# RELAYS.net
KiCad netlist of a schematic drawn in Altium Designer
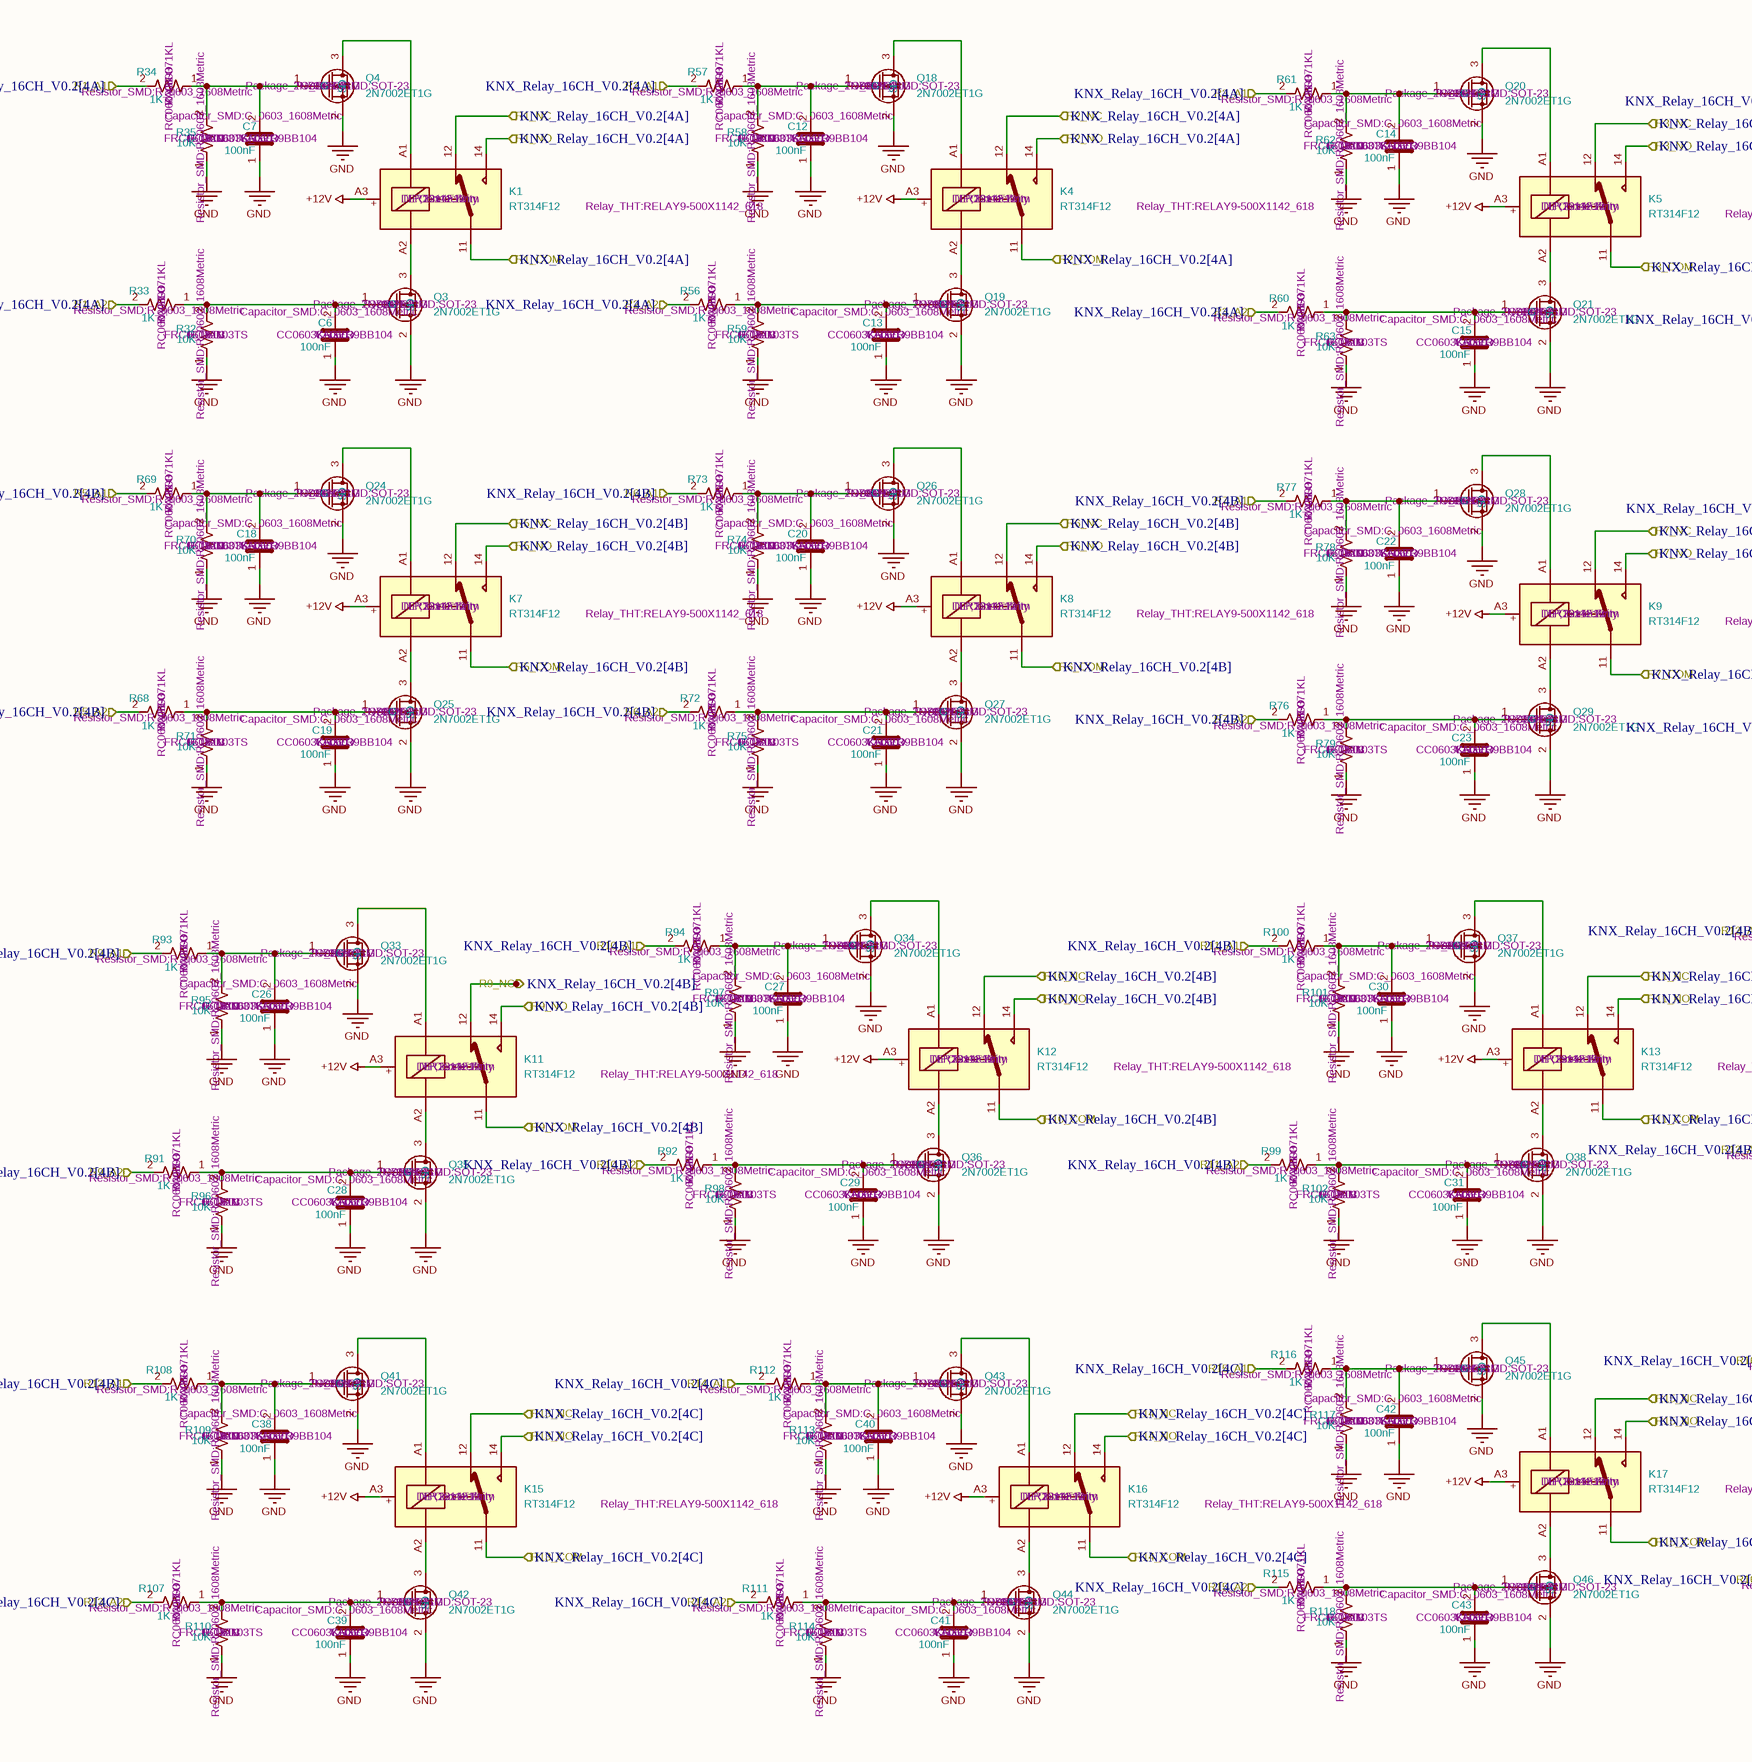
[diagram p0: RELAYS.SchDoc, left]
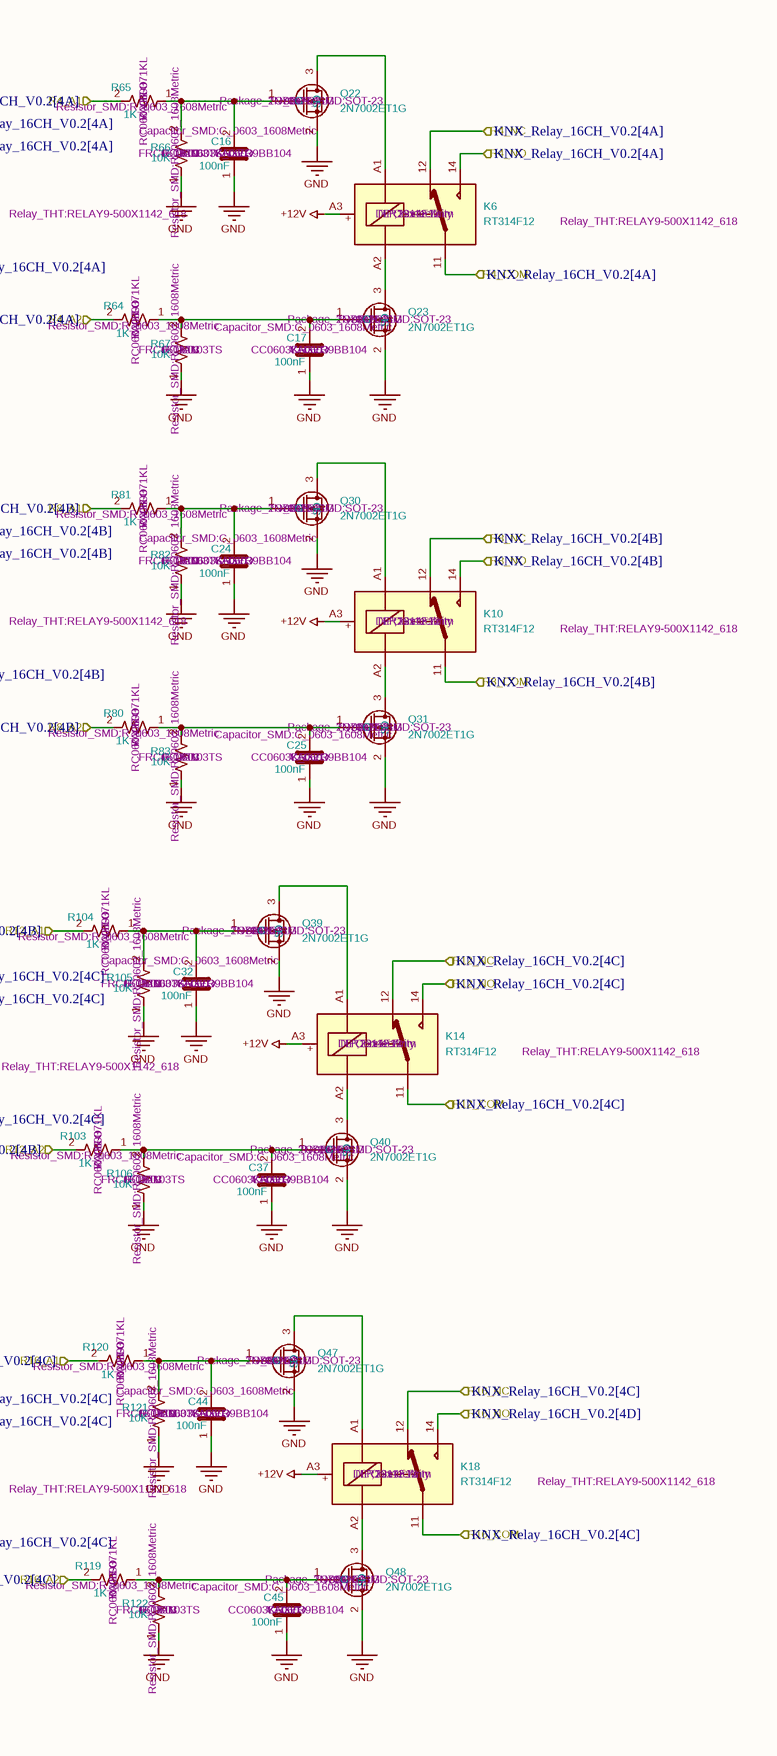
[diagram p1: RELAYS.SchDoc, right]

(export (version "E")
  (design (tool "Eeschema 10.0.6"))
  (components
    (comp (ref "C6")
      (value "100nF")
      (footprint "Capacitor_SMD:C_0603_1608Metric")
      (fields
        (field (name "MANUFACTURER PART NUMBER") "CC0603KRX7R9BB104")
        (field (name "MANUFACTURER") "YAGEO")
        (field (name "PACKAGE") "C_0603")
      )
      (libsource (lib "*") (part "C_3"))
    )
    (comp (ref "C7")
      (value "100nF")
      (footprint "Capacitor_SMD:C_0603_1608Metric")
      (fields
        (field (name "MANUFACTURER PART NUMBER") "CC0603KRX7R9BB104")
        (field (name "MANUFACTURER") "YAGEO")
        (field (name "PACKAGE") "C_0603")
      )
      (libsource (lib "*") (part "C_3"))
    )
    (comp (ref "C12")
      (value "100nF")
      (footprint "Capacitor_SMD:C_0603_1608Metric")
      (fields
        (field (name "MANUFACTURER PART NUMBER") "CC0603KRX7R9BB104")
        (field (name "MANUFACTURER") "YAGEO")
        (field (name "PACKAGE") "C_0603")
      )
      (libsource (lib "*") (part "C_3"))
    )
    (comp (ref "C13")
      (value "100nF")
      (footprint "Capacitor_SMD:C_0603_1608Metric")
      (fields
        (field (name "MANUFACTURER PART NUMBER") "CC0603KRX7R9BB104")
        (field (name "MANUFACTURER") "YAGEO")
        (field (name "PACKAGE") "C_0603")
      )
      (libsource (lib "*") (part "C_3"))
    )
    (comp (ref "C14")
      (value "100nF")
      (footprint "Capacitor_SMD:C_0603_1608Metric")
      (fields
        (field (name "MANUFACTURER PART NUMBER") "CC0603KRX7R9BB104")
        (field (name "MANUFACTURER") "YAGEO")
        (field (name "PACKAGE") "C_0603")
      )
      (libsource (lib "*") (part "C_3"))
    )
    (comp (ref "C15")
      (value "100nF")
      (footprint "Capacitor_SMD:C_0603_1608Metric")
      (fields
        (field (name "MANUFACTURER PART NUMBER") "CC0603KRX7R9BB104")
        (field (name "MANUFACTURER") "YAGEO")
        (field (name "PACKAGE") "C_0603")
      )
      (libsource (lib "*") (part "C_3"))
    )
    (comp (ref "C16")
      (value "100nF")
      (footprint "Capacitor_SMD:C_0603_1608Metric")
      (fields
        (field (name "MANUFACTURER PART NUMBER") "CC0603KRX7R9BB104")
        (field (name "MANUFACTURER") "YAGEO")
        (field (name "PACKAGE") "C_0603")
      )
      (libsource (lib "*") (part "C_3"))
    )
    (comp (ref "C17")
      (value "100nF")
      (footprint "Capacitor_SMD:C_0603_1608Metric")
      (fields
        (field (name "MANUFACTURER PART NUMBER") "CC0603KRX7R9BB104")
        (field (name "MANUFACTURER") "YAGEO")
        (field (name "PACKAGE") "C_0603")
      )
      (libsource (lib "*") (part "C_3"))
    )
    (comp (ref "C18")
      (value "100nF")
      (footprint "Capacitor_SMD:C_0603_1608Metric")
      (fields
        (field (name "MANUFACTURER PART NUMBER") "CC0603KRX7R9BB104")
        (field (name "MANUFACTURER") "YAGEO")
        (field (name "PACKAGE") "C_0603")
      )
      (libsource (lib "*") (part "C_3"))
    )
    (comp (ref "C19")
      (value "100nF")
      (footprint "Capacitor_SMD:C_0603_1608Metric")
      (fields
        (field (name "MANUFACTURER PART NUMBER") "CC0603KRX7R9BB104")
        (field (name "MANUFACTURER") "YAGEO")
        (field (name "PACKAGE") "C_0603")
      )
      (libsource (lib "*") (part "C_3"))
    )
    (comp (ref "C20")
      (value "100nF")
      (footprint "Capacitor_SMD:C_0603_1608Metric")
      (fields
        (field (name "MANUFACTURER PART NUMBER") "CC0603KRX7R9BB104")
        (field (name "MANUFACTURER") "YAGEO")
        (field (name "PACKAGE") "C_0603")
      )
      (libsource (lib "*") (part "C_3"))
    )
    (comp (ref "C21")
      (value "100nF")
      (footprint "Capacitor_SMD:C_0603_1608Metric")
      (fields
        (field (name "MANUFACTURER PART NUMBER") "CC0603KRX7R9BB104")
        (field (name "MANUFACTURER") "YAGEO")
        (field (name "PACKAGE") "C_0603")
      )
      (libsource (lib "*") (part "C_3"))
    )
    (comp (ref "C22")
      (value "100nF")
      (footprint "Capacitor_SMD:C_0603_1608Metric")
      (fields
        (field (name "MANUFACTURER PART NUMBER") "CC0603KRX7R9BB104")
        (field (name "MANUFACTURER") "YAGEO")
        (field (name "PACKAGE") "C_0603")
      )
      (libsource (lib "*") (part "C_3"))
    )
    (comp (ref "C23")
      (value "100nF")
      (footprint "Capacitor_SMD:C_0603_1608Metric")
      (fields
        (field (name "MANUFACTURER PART NUMBER") "CC0603KRX7R9BB104")
        (field (name "MANUFACTURER") "YAGEO")
        (field (name "PACKAGE") "C_0603")
      )
      (libsource (lib "*") (part "C_3"))
    )
    (comp (ref "C24")
      (value "100nF")
      (footprint "Capacitor_SMD:C_0603_1608Metric")
      (fields
        (field (name "MANUFACTURER PART NUMBER") "CC0603KRX7R9BB104")
        (field (name "MANUFACTURER") "YAGEO")
        (field (name "PACKAGE") "C_0603")
      )
      (libsource (lib "*") (part "C_3"))
    )
    (comp (ref "C25")
      (value "100nF")
      (footprint "Capacitor_SMD:C_0603_1608Metric")
      (fields
        (field (name "MANUFACTURER PART NUMBER") "CC0603KRX7R9BB104")
        (field (name "MANUFACTURER") "YAGEO")
        (field (name "PACKAGE") "C_0603")
      )
      (libsource (lib "*") (part "C_3"))
    )
    (comp (ref "C26")
      (value "100nF")
      (footprint "Capacitor_SMD:C_0603_1608Metric")
      (fields
        (field (name "MANUFACTURER PART NUMBER") "CC0603KRX7R9BB104")
        (field (name "MANUFACTURER") "YAGEO")
        (field (name "PACKAGE") "C_0603")
      )
      (libsource (lib "*") (part "C_3"))
    )
    (comp (ref "C27")
      (value "100nF")
      (footprint "Capacitor_SMD:C_0603_1608Metric")
      (fields
        (field (name "MANUFACTURER PART NUMBER") "CC0603KRX7R9BB104")
        (field (name "MANUFACTURER") "YAGEO")
        (field (name "PACKAGE") "C_0603")
      )
      (libsource (lib "*") (part "C_3"))
    )
    (comp (ref "C28")
      (value "100nF")
      (footprint "Capacitor_SMD:C_0603_1608Metric")
      (fields
        (field (name "MANUFACTURER PART NUMBER") "CC0603KRX7R9BB104")
        (field (name "MANUFACTURER") "YAGEO")
        (field (name "PACKAGE") "C_0603")
      )
      (libsource (lib "*") (part "C_3"))
    )
    (comp (ref "C29")
      (value "100nF")
      (footprint "Capacitor_SMD:C_0603_1608Metric")
      (fields
        (field (name "MANUFACTURER PART NUMBER") "CC0603KRX7R9BB104")
        (field (name "MANUFACTURER") "YAGEO")
        (field (name "PACKAGE") "C_0603")
      )
      (libsource (lib "*") (part "C_3"))
    )
    (comp (ref "C30")
      (value "100nF")
      (footprint "Capacitor_SMD:C_0603_1608Metric")
      (fields
        (field (name "MANUFACTURER PART NUMBER") "CC0603KRX7R9BB104")
        (field (name "MANUFACTURER") "YAGEO")
        (field (name "PACKAGE") "C_0603")
      )
      (libsource (lib "*") (part "C_3"))
    )
    (comp (ref "C31")
      (value "100nF")
      (footprint "Capacitor_SMD:C_0603_1608Metric")
      (fields
        (field (name "MANUFACTURER PART NUMBER") "CC0603KRX7R9BB104")
        (field (name "MANUFACTURER") "YAGEO")
        (field (name "PACKAGE") "C_0603")
      )
      (libsource (lib "*") (part "C_3"))
    )
    (comp (ref "C32")
      (value "100nF")
      (footprint "Capacitor_SMD:C_0603_1608Metric")
      (fields
        (field (name "MANUFACTURER PART NUMBER") "CC0603KRX7R9BB104")
        (field (name "MANUFACTURER") "YAGEO")
        (field (name "PACKAGE") "C_0603")
      )
      (libsource (lib "*") (part "C_3"))
    )
    (comp (ref "C37")
      (value "100nF")
      (footprint "Capacitor_SMD:C_0603_1608Metric")
      (fields
        (field (name "MANUFACTURER PART NUMBER") "CC0603KRX7R9BB104")
        (field (name "MANUFACTURER") "YAGEO")
        (field (name "PACKAGE") "C_0603")
      )
      (libsource (lib "*") (part "C_3"))
    )
    (comp (ref "C38")
      (value "100nF")
      (footprint "Capacitor_SMD:C_0603_1608Metric")
      (fields
        (field (name "MANUFACTURER PART NUMBER") "CC0603KRX7R9BB104")
        (field (name "MANUFACTURER") "YAGEO")
        (field (name "PACKAGE") "C_0603")
      )
      (libsource (lib "*") (part "C_3"))
    )
    (comp (ref "C39")
      (value "100nF")
      (footprint "Capacitor_SMD:C_0603_1608Metric")
      (fields
        (field (name "MANUFACTURER PART NUMBER") "CC0603KRX7R9BB104")
        (field (name "MANUFACTURER") "YAGEO")
        (field (name "PACKAGE") "C_0603")
      )
      (libsource (lib "*") (part "C_3"))
    )
    (comp (ref "C40")
      (value "100nF")
      (footprint "Capacitor_SMD:C_0603_1608Metric")
      (fields
        (field (name "MANUFACTURER PART NUMBER") "CC0603KRX7R9BB104")
        (field (name "MANUFACTURER") "YAGEO")
        (field (name "PACKAGE") "C_0603")
      )
      (libsource (lib "*") (part "C_3"))
    )
    (comp (ref "C41")
      (value "100nF")
      (footprint "Capacitor_SMD:C_0603_1608Metric")
      (fields
        (field (name "MANUFACTURER PART NUMBER") "CC0603KRX7R9BB104")
        (field (name "MANUFACTURER") "YAGEO")
        (field (name "PACKAGE") "C_0603")
      )
      (libsource (lib "*") (part "C_3"))
    )
    (comp (ref "C42")
      (value "100nF")
      (footprint "Capacitor_SMD:C_0603_1608Metric")
      (fields
        (field (name "MANUFACTURER PART NUMBER") "CC0603KRX7R9BB104")
        (field (name "MANUFACTURER") "YAGEO")
        (field (name "PACKAGE") "C_0603")
      )
      (libsource (lib "*") (part "C_3"))
    )
    (comp (ref "C43")
      (value "100nF")
      (footprint "Capacitor_SMD:C_0603_1608Metric")
      (fields
        (field (name "MANUFACTURER PART NUMBER") "CC0603KRX7R9BB104")
        (field (name "MANUFACTURER") "YAGEO")
        (field (name "PACKAGE") "C_0603")
      )
      (libsource (lib "*") (part "C_3"))
    )
    (comp (ref "C44")
      (value "100nF")
      (footprint "Capacitor_SMD:C_0603_1608Metric")
      (fields
        (field (name "MANUFACTURER PART NUMBER") "CC0603KRX7R9BB104")
        (field (name "MANUFACTURER") "YAGEO")
        (field (name "PACKAGE") "C_0603")
      )
      (libsource (lib "*") (part "C_3"))
    )
    (comp (ref "C45")
      (value "100nF")
      (footprint "Capacitor_SMD:C_0603_1608Metric")
      (fields
        (field (name "MANUFACTURER PART NUMBER") "CC0603KRX7R9BB104")
        (field (name "MANUFACTURER") "YAGEO")
        (field (name "PACKAGE") "C_0603")
      )
      (libsource (lib "*") (part "C_3"))
    )
    (comp (ref "K1")
      (value "RT314F12")
      (footprint "Relay_THT:RELAY9-500X1142_618")
      (fields
        (field (name "MANUFACTURER PART NUMBER") "RT314F12")
        (field (name "MANUFACTURER") "TE Connectivity")
        (field (name "PACKAGE") "DIP,29x12.7mm")
      )
      (libsource (lib "Me_Library") (part "RT314A03"))
    )
    (comp (ref "K4")
      (value "RT314F12")
      (footprint "Relay_THT:RELAY9-500X1142_618")
      (fields
        (field (name "MANUFACTURER PART NUMBER") "RT314F12")
        (field (name "MANUFACTURER") "TE Connectivity")
        (field (name "PACKAGE") "DIP,29x12.7mm")
      )
      (libsource (lib "Me_Library") (part "RT314A03"))
    )
    (comp (ref "K5")
      (value "RT314F12")
      (footprint "Relay_THT:RELAY9-500X1142_618")
      (fields
        (field (name "MANUFACTURER PART NUMBER") "RT314F12")
        (field (name "MANUFACTURER") "TE Connectivity")
        (field (name "PACKAGE") "DIP,29x12.7mm")
      )
      (libsource (lib "Me_Library") (part "RT314A03"))
    )
    (comp (ref "K6")
      (value "RT314F12")
      (footprint "Relay_THT:RELAY9-500X1142_618")
      (fields
        (field (name "MANUFACTURER PART NUMBER") "RT314F12")
        (field (name "MANUFACTURER") "TE Connectivity")
        (field (name "PACKAGE") "DIP,29x12.7mm")
      )
      (libsource (lib "Me_Library") (part "RT314A03"))
    )
    (comp (ref "K7")
      (value "RT314F12")
      (footprint "Relay_THT:RELAY9-500X1142_618")
      (fields
        (field (name "MANUFACTURER PART NUMBER") "RT314F12")
        (field (name "MANUFACTURER") "TE Connectivity")
        (field (name "PACKAGE") "DIP,29x12.7mm")
      )
      (libsource (lib "Me_Library") (part "RT314A03"))
    )
    (comp (ref "K8")
      (value "RT314F12")
      (footprint "Relay_THT:RELAY9-500X1142_618")
      (fields
        (field (name "MANUFACTURER PART NUMBER") "RT314F12")
        (field (name "MANUFACTURER") "TE Connectivity")
        (field (name "PACKAGE") "DIP,29x12.7mm")
      )
      (libsource (lib "Me_Library") (part "RT314A03"))
    )
    (comp (ref "K9")
      (value "RT314F12")
      (footprint "Relay_THT:RELAY9-500X1142_618")
      (fields
        (field (name "MANUFACTURER PART NUMBER") "RT314F12")
        (field (name "MANUFACTURER") "TE Connectivity")
        (field (name "PACKAGE") "DIP,29x12.7mm")
      )
      (libsource (lib "Me_Library") (part "RT314A03"))
    )
    (comp (ref "K10")
      (value "RT314F12")
      (footprint "Relay_THT:RELAY9-500X1142_618")
      (fields
        (field (name "MANUFACTURER PART NUMBER") "RT314F12")
        (field (name "MANUFACTURER") "TE Connectivity")
        (field (name "PACKAGE") "DIP,29x12.7mm")
      )
      (libsource (lib "Me_Library") (part "RT314A03"))
    )
    (comp (ref "K11")
      (value "RT314F12")
      (footprint "Relay_THT:RELAY9-500X1142_618")
      (fields
        (field (name "MANUFACTURER PART NUMBER") "RT314F12")
        (field (name "MANUFACTURER") "TE Connectivity")
        (field (name "PACKAGE") "DIP,29x12.7mm")
      )
      (libsource (lib "Me_Library") (part "RT314A03"))
    )
    (comp (ref "K12")
      (value "RT314F12")
      (footprint "Relay_THT:RELAY9-500X1142_618")
      (fields
        (field (name "MANUFACTURER PART NUMBER") "RT314F12")
        (field (name "MANUFACTURER") "TE Connectivity")
        (field (name "PACKAGE") "DIP,29x12.7mm")
      )
      (libsource (lib "Me_Library") (part "RT314A03"))
    )
    (comp (ref "K13")
      (value "RT314F12")
      (footprint "Relay_THT:RELAY9-500X1142_618")
      (fields
        (field (name "MANUFACTURER PART NUMBER") "RT314F12")
        (field (name "MANUFACTURER") "TE Connectivity")
        (field (name "PACKAGE") "DIP,29x12.7mm")
      )
      (libsource (lib "Me_Library") (part "RT314A03"))
    )
    (comp (ref "K14")
      (value "RT314F12")
      (footprint "Relay_THT:RELAY9-500X1142_618")
      (fields
        (field (name "MANUFACTURER PART NUMBER") "RT314F12")
        (field (name "MANUFACTURER") "TE Connectivity")
        (field (name "PACKAGE") "DIP,29x12.7mm")
      )
      (libsource (lib "Me_Library") (part "RT314A03"))
    )
    (comp (ref "K15")
      (value "RT314F12")
      (footprint "Relay_THT:RELAY9-500X1142_618")
      (fields
        (field (name "MANUFACTURER PART NUMBER") "RT314F12")
        (field (name "MANUFACTURER") "TE Connectivity")
        (field (name "PACKAGE") "DIP,29x12.7mm")
      )
      (libsource (lib "Me_Library") (part "RT314A03"))
    )
    (comp (ref "K16")
      (value "RT314F12")
      (footprint "Relay_THT:RELAY9-500X1142_618")
      (fields
        (field (name "MANUFACTURER PART NUMBER") "RT314F12")
        (field (name "MANUFACTURER") "TE Connectivity")
        (field (name "PACKAGE") "DIP,29x12.7mm")
      )
      (libsource (lib "Me_Library") (part "RT314A03"))
    )
    (comp (ref "K17")
      (value "RT314F12")
      (footprint "Relay_THT:RELAY9-500X1142_618")
      (fields
        (field (name "MANUFACTURER PART NUMBER") "RT314F12")
        (field (name "MANUFACTURER") "TE Connectivity")
        (field (name "PACKAGE") "DIP,29x12.7mm")
      )
      (libsource (lib "Me_Library") (part "RT314A03"))
    )
    (comp (ref "K18")
      (value "RT314F12")
      (footprint "Relay_THT:RELAY9-500X1142_618")
      (fields
        (field (name "MANUFACTURER PART NUMBER") "RT314F12")
        (field (name "MANUFACTURER") "TE Connectivity")
        (field (name "PACKAGE") "DIP,29x12.7mm")
      )
      (libsource (lib "Me_Library") (part "RT314A03"))
    )
    (comp (ref "Q3")
      (value "2N7002ET1G")
      (footprint "Package_TO_SOT_SMD:SOT-23")
      (fields
        (field (name "MANUFACTURER PART NUMBER") "2N7002ET1G")
        (field (name "MANUFACTURER") "onsemi")
        (field (name "PACKAGE") "SOT-23")
      )
      (libsource (lib "Transistor_FET_Other") (part "Q_NMOS_Depletion_GSD"))
    )
    (comp (ref "Q4")
      (value "2N7002ET1G")
      (footprint "Package_TO_SOT_SMD:SOT-23")
      (fields
        (field (name "MANUFACTURER PART NUMBER") "2N7002ET1G")
        (field (name "MANUFACTURER") "onsemi")
        (field (name "PACKAGE") "SOT-23")
      )
      (libsource (lib "Transistor_FET_Other") (part "Q_NMOS_Depletion_GSD"))
    )
    (comp (ref "Q18")
      (value "2N7002ET1G")
      (footprint "Package_TO_SOT_SMD:SOT-23")
      (fields
        (field (name "MANUFACTURER PART NUMBER") "2N7002ET1G")
        (field (name "MANUFACTURER") "onsemi")
        (field (name "PACKAGE") "SOT-23")
      )
      (libsource (lib "Transistor_FET_Other") (part "Q_NMOS_Depletion_GSD"))
    )
    (comp (ref "Q19")
      (value "2N7002ET1G")
      (footprint "Package_TO_SOT_SMD:SOT-23")
      (fields
        (field (name "MANUFACTURER PART NUMBER") "2N7002ET1G")
        (field (name "MANUFACTURER") "onsemi")
        (field (name "PACKAGE") "SOT-23")
      )
      (libsource (lib "Transistor_FET_Other") (part "Q_NMOS_Depletion_GSD"))
    )
    (comp (ref "Q20")
      (value "2N7002ET1G")
      (footprint "Package_TO_SOT_SMD:SOT-23")
      (fields
        (field (name "MANUFACTURER PART NUMBER") "2N7002ET1G")
        (field (name "MANUFACTURER") "onsemi")
        (field (name "PACKAGE") "SOT-23")
      )
      (libsource (lib "Transistor_FET_Other") (part "Q_NMOS_Depletion_GSD"))
    )
    (comp (ref "Q21")
      (value "2N7002ET1G")
      (footprint "Package_TO_SOT_SMD:SOT-23")
      (fields
        (field (name "MANUFACTURER PART NUMBER") "2N7002ET1G")
        (field (name "MANUFACTURER") "onsemi")
        (field (name "PACKAGE") "SOT-23")
      )
      (libsource (lib "Transistor_FET_Other") (part "Q_NMOS_Depletion_GSD"))
    )
    (comp (ref "Q22")
      (value "2N7002ET1G")
      (footprint "Package_TO_SOT_SMD:SOT-23")
      (fields
        (field (name "MANUFACTURER PART NUMBER") "2N7002ET1G")
        (field (name "MANUFACTURER") "onsemi")
        (field (name "PACKAGE") "SOT-23")
      )
      (libsource (lib "Transistor_FET_Other") (part "Q_NMOS_Depletion_GSD"))
    )
    (comp (ref "Q23")
      (value "2N7002ET1G")
      (footprint "Package_TO_SOT_SMD:SOT-23")
      (fields
        (field (name "MANUFACTURER PART NUMBER") "2N7002ET1G")
        (field (name "MANUFACTURER") "onsemi")
        (field (name "PACKAGE") "SOT-23")
      )
      (libsource (lib "Transistor_FET_Other") (part "Q_NMOS_Depletion_GSD"))
    )
    (comp (ref "Q24")
      (value "2N7002ET1G")
      (footprint "Package_TO_SOT_SMD:SOT-23")
      (fields
        (field (name "MANUFACTURER PART NUMBER") "2N7002ET1G")
        (field (name "MANUFACTURER") "onsemi")
        (field (name "PACKAGE") "SOT-23")
      )
      (libsource (lib "Transistor_FET_Other") (part "Q_NMOS_Depletion_GSD"))
    )
    (comp (ref "Q25")
      (value "2N7002ET1G")
      (footprint "Package_TO_SOT_SMD:SOT-23")
      (fields
        (field (name "MANUFACTURER PART NUMBER") "2N7002ET1G")
        (field (name "MANUFACTURER") "onsemi")
        (field (name "PACKAGE") "SOT-23")
      )
      (libsource (lib "Transistor_FET_Other") (part "Q_NMOS_Depletion_GSD"))
    )
    (comp (ref "Q26")
      (value "2N7002ET1G")
      (footprint "Package_TO_SOT_SMD:SOT-23")
      (fields
        (field (name "MANUFACTURER PART NUMBER") "2N7002ET1G")
        (field (name "MANUFACTURER") "onsemi")
        (field (name "PACKAGE") "SOT-23")
      )
      (libsource (lib "Transistor_FET_Other") (part "Q_NMOS_Depletion_GSD"))
    )
    (comp (ref "Q27")
      (value "2N7002ET1G")
      (footprint "Package_TO_SOT_SMD:SOT-23")
      (fields
        (field (name "MANUFACTURER PART NUMBER") "2N7002ET1G")
        (field (name "MANUFACTURER") "onsemi")
        (field (name "PACKAGE") "SOT-23")
      )
      (libsource (lib "Transistor_FET_Other") (part "Q_NMOS_Depletion_GSD"))
    )
    (comp (ref "Q28")
      (value "2N7002ET1G")
      (footprint "Package_TO_SOT_SMD:SOT-23")
      (fields
        (field (name "MANUFACTURER PART NUMBER") "2N7002ET1G")
        (field (name "MANUFACTURER") "onsemi")
        (field (name "PACKAGE") "SOT-23")
      )
      (libsource (lib "Transistor_FET_Other") (part "Q_NMOS_Depletion_GSD"))
    )
    (comp (ref "Q29")
      (value "2N7002ET1G")
      (footprint "Package_TO_SOT_SMD:SOT-23")
      (fields
        (field (name "MANUFACTURER PART NUMBER") "2N7002ET1G")
        (field (name "MANUFACTURER") "onsemi")
        (field (name "PACKAGE") "SOT-23")
      )
      (libsource (lib "Transistor_FET_Other") (part "Q_NMOS_Depletion_GSD"))
    )
    (comp (ref "Q30")
      (value "2N7002ET1G")
      (footprint "Package_TO_SOT_SMD:SOT-23")
      (fields
        (field (name "MANUFACTURER PART NUMBER") "2N7002ET1G")
        (field (name "MANUFACTURER") "onsemi")
        (field (name "PACKAGE") "SOT-23")
      )
      (libsource (lib "Transistor_FET_Other") (part "Q_NMOS_Depletion_GSD"))
    )
    (comp (ref "Q31")
      (value "2N7002ET1G")
      (footprint "Package_TO_SOT_SMD:SOT-23")
      (fields
        (field (name "MANUFACTURER PART NUMBER") "2N7002ET1G")
        (field (name "MANUFACTURER") "onsemi")
        (field (name "PACKAGE") "SOT-23")
      )
      (libsource (lib "Transistor_FET_Other") (part "Q_NMOS_Depletion_GSD"))
    )
    (comp (ref "Q33")
      (value "2N7002ET1G")
      (footprint "Package_TO_SOT_SMD:SOT-23")
      (fields
        (field (name "MANUFACTURER PART NUMBER") "2N7002ET1G")
        (field (name "MANUFACTURER") "onsemi")
        (field (name "PACKAGE") "SOT-23")
      )
      (libsource (lib "Transistor_FET_Other") (part "Q_NMOS_Depletion_GSD"))
    )
    (comp (ref "Q34")
      (value "2N7002ET1G")
      (footprint "Package_TO_SOT_SMD:SOT-23")
      (fields
        (field (name "MANUFACTURER PART NUMBER") "2N7002ET1G")
        (field (name "MANUFACTURER") "onsemi")
        (field (name "PACKAGE") "SOT-23")
      )
      (libsource (lib "Transistor_FET_Other") (part "Q_NMOS_Depletion_GSD"))
    )
    (comp (ref "Q35")
      (value "2N7002ET1G")
      (footprint "Package_TO_SOT_SMD:SOT-23")
      (fields
        (field (name "MANUFACTURER PART NUMBER") "2N7002ET1G")
        (field (name "MANUFACTURER") "onsemi")
        (field (name "PACKAGE") "SOT-23")
      )
      (libsource (lib "Transistor_FET_Other") (part "Q_NMOS_Depletion_GSD"))
    )
    (comp (ref "Q36")
      (value "2N7002ET1G")
      (footprint "Package_TO_SOT_SMD:SOT-23")
      (fields
        (field (name "MANUFACTURER PART NUMBER") "2N7002ET1G")
        (field (name "MANUFACTURER") "onsemi")
        (field (name "PACKAGE") "SOT-23")
      )
      (libsource (lib "Transistor_FET_Other") (part "Q_NMOS_Depletion_GSD"))
    )
    (comp (ref "Q37")
      (value "2N7002ET1G")
      (footprint "Package_TO_SOT_SMD:SOT-23")
      (fields
        (field (name "MANUFACTURER PART NUMBER") "2N7002ET1G")
        (field (name "MANUFACTURER") "onsemi")
        (field (name "PACKAGE") "SOT-23")
      )
      (libsource (lib "Transistor_FET_Other") (part "Q_NMOS_Depletion_GSD"))
    )
    (comp (ref "Q38")
      (value "2N7002ET1G")
      (footprint "Package_TO_SOT_SMD:SOT-23")
      (fields
        (field (name "MANUFACTURER PART NUMBER") "2N7002ET1G")
        (field (name "MANUFACTURER") "onsemi")
        (field (name "PACKAGE") "SOT-23")
      )
      (libsource (lib "Transistor_FET_Other") (part "Q_NMOS_Depletion_GSD"))
    )
    (comp (ref "Q39")
      (value "2N7002ET1G")
      (footprint "Package_TO_SOT_SMD:SOT-23")
      (fields
        (field (name "MANUFACTURER PART NUMBER") "2N7002ET1G")
        (field (name "MANUFACTURER") "onsemi")
        (field (name "PACKAGE") "SOT-23")
      )
      (libsource (lib "Transistor_FET_Other") (part "Q_NMOS_Depletion_GSD"))
    )
    (comp (ref "Q40")
      (value "2N7002ET1G")
      (footprint "Package_TO_SOT_SMD:SOT-23")
      (fields
        (field (name "MANUFACTURER PART NUMBER") "2N7002ET1G")
        (field (name "MANUFACTURER") "onsemi")
        (field (name "PACKAGE") "SOT-23")
      )
      (libsource (lib "Transistor_FET_Other") (part "Q_NMOS_Depletion_GSD"))
    )
    (comp (ref "Q41")
      (value "2N7002ET1G")
      (footprint "Package_TO_SOT_SMD:SOT-23")
      (fields
        (field (name "MANUFACTURER PART NUMBER") "2N7002ET1G")
        (field (name "MANUFACTURER") "onsemi")
        (field (name "PACKAGE") "SOT-23")
      )
      (libsource (lib "Transistor_FET_Other") (part "Q_NMOS_Depletion_GSD"))
    )
    (comp (ref "Q42")
      (value "2N7002ET1G")
      (footprint "Package_TO_SOT_SMD:SOT-23")
      (fields
        (field (name "MANUFACTURER PART NUMBER") "2N7002ET1G")
        (field (name "MANUFACTURER") "onsemi")
        (field (name "PACKAGE") "SOT-23")
      )
      (libsource (lib "Transistor_FET_Other") (part "Q_NMOS_Depletion_GSD"))
    )
    (comp (ref "Q43")
      (value "2N7002ET1G")
      (footprint "Package_TO_SOT_SMD:SOT-23")
      (fields
        (field (name "MANUFACTURER PART NUMBER") "2N7002ET1G")
        (field (name "MANUFACTURER") "onsemi")
        (field (name "PACKAGE") "SOT-23")
      )
      (libsource (lib "Transistor_FET_Other") (part "Q_NMOS_Depletion_GSD"))
    )
    (comp (ref "Q44")
      (value "2N7002ET1G")
      (footprint "Package_TO_SOT_SMD:SOT-23")
      (fields
        (field (name "MANUFACTURER PART NUMBER") "2N7002ET1G")
        (field (name "MANUFACTURER") "onsemi")
        (field (name "PACKAGE") "SOT-23")
      )
      (libsource (lib "Transistor_FET_Other") (part "Q_NMOS_Depletion_GSD"))
    )
    (comp (ref "Q45")
      (value "2N7002ET1G")
      (footprint "Package_TO_SOT_SMD:SOT-23")
      (fields
        (field (name "MANUFACTURER PART NUMBER") "2N7002ET1G")
        (field (name "MANUFACTURER") "onsemi")
        (field (name "PACKAGE") "SOT-23")
      )
      (libsource (lib "Transistor_FET_Other") (part "Q_NMOS_Depletion_GSD"))
    )
    (comp (ref "Q46")
      (value "2N7002ET1G")
      (footprint "Package_TO_SOT_SMD:SOT-23")
      (fields
        (field (name "MANUFACTURER PART NUMBER") "2N7002ET1G")
        (field (name "MANUFACTURER") "onsemi")
        (field (name "PACKAGE") "SOT-23")
      )
      (libsource (lib "Transistor_FET_Other") (part "Q_NMOS_Depletion_GSD"))
    )
    (comp (ref "Q47")
      (value "2N7002ET1G")
      (footprint "Package_TO_SOT_SMD:SOT-23")
      (fields
        (field (name "MANUFACTURER PART NUMBER") "2N7002ET1G")
        (field (name "MANUFACTURER") "onsemi")
        (field (name "PACKAGE") "SOT-23")
      )
      (libsource (lib "Transistor_FET_Other") (part "Q_NMOS_Depletion_GSD"))
    )
    (comp (ref "Q48")
      (value "2N7002ET1G")
      (footprint "Package_TO_SOT_SMD:SOT-23")
      (fields
        (field (name "MANUFACTURER PART NUMBER") "2N7002ET1G")
        (field (name "MANUFACTURER") "onsemi")
        (field (name "PACKAGE") "SOT-23")
      )
      (libsource (lib "Transistor_FET_Other") (part "Q_NMOS_Depletion_GSD"))
    )
    (comp (ref "R32")
      (value "10K")
      (footprint "Resistor_SMD:R_0603_1608Metric")
      (fields
        (field (name "MANUFACTURER PART NUMBER") "FRC0603J103TS")
        (field (name "MANUFACTURER") "FOJAN")
        (field (name "PACKAGE") "R_0603")
      )
      (libsource (lib "Device") (part "R_US"))
    )
    (comp (ref "R33")
      (value "1K")
      (footprint "Resistor_SMD:R_0603_1608Metric")
      (fields
        (field (name "MANUFACTURER PART NUMBER") "RC0603JR-071KL")
        (field (name "MANUFACTURER") "YAGEO")
        (field (name "PACKAGE") "R_0603")
      )
      (libsource (lib "Device") (part "R_US"))
    )
    (comp (ref "R34")
      (value "1K")
      (footprint "Resistor_SMD:R_0603_1608Metric")
      (fields
        (field (name "MANUFACTURER PART NUMBER") "RC0603JR-071KL")
        (field (name "MANUFACTURER") "YAGEO")
        (field (name "PACKAGE") "R_0603")
      )
      (libsource (lib "Device") (part "R_US"))
    )
    (comp (ref "R35")
      (value "10K")
      (footprint "Resistor_SMD:R_0603_1608Metric")
      (fields
        (field (name "MANUFACTURER PART NUMBER") "FRC0603J103TS")
        (field (name "MANUFACTURER") "FOJAN")
        (field (name "PACKAGE") "R_0603")
      )
      (libsource (lib "Device") (part "R_US"))
    )
    (comp (ref "R56")
      (value "1K")
      (footprint "Resistor_SMD:R_0603_1608Metric")
      (fields
        (field (name "MANUFACTURER PART NUMBER") "RC0603JR-071KL")
        (field (name "MANUFACTURER") "YAGEO")
        (field (name "PACKAGE") "R_0603")
      )
      (libsource (lib "Device") (part "R_US"))
    )
    (comp (ref "R57")
      (value "1K")
      (footprint "Resistor_SMD:R_0603_1608Metric")
      (fields
        (field (name "MANUFACTURER PART NUMBER") "RC0603JR-071KL")
        (field (name "MANUFACTURER") "YAGEO")
        (field (name "PACKAGE") "R_0603")
      )
      (libsource (lib "Device") (part "R_US"))
    )
    (comp (ref "R58")
      (value "10K")
      (footprint "Resistor_SMD:R_0603_1608Metric")
      (fields
        (field (name "MANUFACTURER PART NUMBER") "FRC0603J103TS")
        (field (name "MANUFACTURER") "FOJAN")
        (field (name "PACKAGE") "R_0603")
      )
      (libsource (lib "Device") (part "R_US"))
    )
    (comp (ref "R59")
      (value "10K")
      (footprint "Resistor_SMD:R_0603_1608Metric")
      (fields
        (field (name "MANUFACTURER PART NUMBER") "FRC0603J103TS")
        (field (name "MANUFACTURER") "FOJAN")
        (field (name "PACKAGE") "R_0603")
      )
      (libsource (lib "Device") (part "R_US"))
    )
    (comp (ref "R60")
      (value "1K")
      (footprint "Resistor_SMD:R_0603_1608Metric")
      (fields
        (field (name "MANUFACTURER PART NUMBER") "RC0603JR-071KL")
        (field (name "MANUFACTURER") "YAGEO")
        (field (name "PACKAGE") "R_0603")
      )
      (libsource (lib "Device") (part "R_US"))
    )
    (comp (ref "R61")
      (value "1K")
      (footprint "Resistor_SMD:R_0603_1608Metric")
      (fields
        (field (name "MANUFACTURER PART NUMBER") "RC0603JR-071KL")
        (field (name "MANUFACTURER") "YAGEO")
        (field (name "PACKAGE") "R_0603")
      )
      (libsource (lib "Device") (part "R_US"))
    )
    (comp (ref "R62")
      (value "10K")
      (footprint "Resistor_SMD:R_0603_1608Metric")
      (fields
        (field (name "MANUFACTURER PART NUMBER") "FRC0603J103TS")
        (field (name "MANUFACTURER") "FOJAN")
        (field (name "PACKAGE") "R_0603")
      )
      (libsource (lib "Device") (part "R_US"))
    )
    (comp (ref "R63")
      (value "10K")
      (footprint "Resistor_SMD:R_0603_1608Metric")
      (fields
        (field (name "MANUFACTURER PART NUMBER") "FRC0603J103TS")
        (field (name "MANUFACTURER") "FOJAN")
        (field (name "PACKAGE") "R_0603")
      )
      (libsource (lib "Device") (part "R_US"))
    )
    (comp (ref "R64")
      (value "1K")
      (footprint "Resistor_SMD:R_0603_1608Metric")
      (fields
        (field (name "MANUFACTURER PART NUMBER") "RC0603JR-071KL")
        (field (name "MANUFACTURER") "YAGEO")
        (field (name "PACKAGE") "R_0603")
      )
      (libsource (lib "Device") (part "R_US"))
    )
    (comp (ref "R65")
      (value "1K")
      (footprint "Resistor_SMD:R_0603_1608Metric")
      (fields
        (field (name "MANUFACTURER PART NUMBER") "RC0603JR-071KL")
        (field (name "MANUFACTURER") "YAGEO")
        (field (name "PACKAGE") "R_0603")
      )
      (libsource (lib "Device") (part "R_US"))
    )
    (comp (ref "R66")
      (value "10K")
      (footprint "Resistor_SMD:R_0603_1608Metric")
      (fields
        (field (name "MANUFACTURER PART NUMBER") "FRC0603J103TS")
        (field (name "MANUFACTURER") "FOJAN")
        (field (name "PACKAGE") "R_0603")
      )
      (libsource (lib "Device") (part "R_US"))
    )
    (comp (ref "R67")
      (value "10K")
      (footprint "Resistor_SMD:R_0603_1608Metric")
      (fields
        (field (name "MANUFACTURER PART NUMBER") "FRC0603J103TS")
        (field (name "MANUFACTURER") "FOJAN")
        (field (name "PACKAGE") "R_0603")
      )
      (libsource (lib "Device") (part "R_US"))
    )
    (comp (ref "R68")
      (value "1K")
      (footprint "Resistor_SMD:R_0603_1608Metric")
      (fields
        (field (name "MANUFACTURER PART NUMBER") "RC0603JR-071KL")
        (field (name "MANUFACTURER") "YAGEO")
        (field (name "PACKAGE") "R_0603")
      )
      (libsource (lib "Device") (part "R_US"))
    )
    (comp (ref "R69")
      (value "1K")
      (footprint "Resistor_SMD:R_0603_1608Metric")
      (fields
        (field (name "MANUFACTURER PART NUMBER") "RC0603JR-071KL")
        (field (name "MANUFACTURER") "YAGEO")
        (field (name "PACKAGE") "R_0603")
      )
      (libsource (lib "Device") (part "R_US"))
    )
    (comp (ref "R70")
      (value "10K")
      (footprint "Resistor_SMD:R_0603_1608Metric")
      (fields
        (field (name "MANUFACTURER PART NUMBER") "FRC0603J103TS")
        (field (name "MANUFACTURER") "FOJAN")
        (field (name "PACKAGE") "R_0603")
      )
      (libsource (lib "Device") (part "R_US"))
    )
    (comp (ref "R71")
      (value "10K")
      (footprint "Resistor_SMD:R_0603_1608Metric")
      (fields
        (field (name "MANUFACTURER PART NUMBER") "FRC0603J103TS")
        (field (name "MANUFACTURER") "FOJAN")
        (field (name "PACKAGE") "R_0603")
      )
      (libsource (lib "Device") (part "R_US"))
    )
    (comp (ref "R72")
      (value "1K")
      (footprint "Resistor_SMD:R_0603_1608Metric")
      (fields
        (field (name "MANUFACTURER PART NUMBER") "RC0603JR-071KL")
        (field (name "MANUFACTURER") "YAGEO")
        (field (name "PACKAGE") "R_0603")
      )
      (libsource (lib "Device") (part "R_US"))
    )
    (comp (ref "R73")
      (value "1K")
      (footprint "Resistor_SMD:R_0603_1608Metric")
      (fields
        (field (name "MANUFACTURER PART NUMBER") "RC0603JR-071KL")
        (field (name "MANUFACTURER") "YAGEO")
        (field (name "PACKAGE") "R_0603")
      )
      (libsource (lib "Device") (part "R_US"))
    )
    (comp (ref "R74")
      (value "10K")
      (footprint "Resistor_SMD:R_0603_1608Metric")
      (fields
        (field (name "MANUFACTURER PART NUMBER") "FRC0603J103TS")
        (field (name "MANUFACTURER") "FOJAN")
        (field (name "PACKAGE") "R_0603")
      )
      (libsource (lib "Device") (part "R_US"))
    )
    (comp (ref "R75")
      (value "10K")
      (footprint "Resistor_SMD:R_0603_1608Metric")
      (fields
        (field (name "MANUFACTURER PART NUMBER") "FRC0603J103TS")
        (field (name "MANUFACTURER") "FOJAN")
        (field (name "PACKAGE") "R_0603")
      )
      (libsource (lib "Device") (part "R_US"))
    )
    (comp (ref "R76")
      (value "1K")
      (footprint "Resistor_SMD:R_0603_1608Metric")
      (fields
        (field (name "MANUFACTURER PART NUMBER") "RC0603JR-071KL")
        (field (name "MANUFACTURER") "YAGEO")
        (field (name "PACKAGE") "R_0603")
      )
      (libsource (lib "Device") (part "R_US"))
    )
    (comp (ref "R77")
      (value "1K")
      (footprint "Resistor_SMD:R_0603_1608Metric")
      (fields
        (field (name "MANUFACTURER PART NUMBER") "RC0603JR-071KL")
        (field (name "MANUFACTURER") "YAGEO")
        (field (name "PACKAGE") "R_0603")
      )
      (libsource (lib "Device") (part "R_US"))
    )
    (comp (ref "R78")
      (value "10K")
      (footprint "Resistor_SMD:R_0603_1608Metric")
      (fields
        (field (name "MANUFACTURER PART NUMBER") "FRC0603J103TS")
        (field (name "MANUFACTURER") "FOJAN")
        (field (name "PACKAGE") "R_0603")
      )
      (libsource (lib "Device") (part "R_US"))
    )
    (comp (ref "R79")
      (value "10K")
      (footprint "Resistor_SMD:R_0603_1608Metric")
      (fields
        (field (name "MANUFACTURER PART NUMBER") "FRC0603J103TS")
        (field (name "MANUFACTURER") "FOJAN")
        (field (name "PACKAGE") "R_0603")
      )
      (libsource (lib "Device") (part "R_US"))
    )
    (comp (ref "R80")
      (value "1K")
      (footprint "Resistor_SMD:R_0603_1608Metric")
      (fields
        (field (name "MANUFACTURER PART NUMBER") "RC0603JR-071KL")
        (field (name "MANUFACTURER") "YAGEO")
        (field (name "PACKAGE") "R_0603")
      )
      (libsource (lib "Device") (part "R_US"))
    )
    (comp (ref "R81")
      (value "1K")
      (footprint "Resistor_SMD:R_0603_1608Metric")
      (fields
        (field (name "MANUFACTURER PART NUMBER") "RC0603JR-071KL")
        (field (name "MANUFACTURER") "YAGEO")
        (field (name "PACKAGE") "R_0603")
      )
      (libsource (lib "Device") (part "R_US"))
    )
    (comp (ref "R82")
      (value "10K")
      (footprint "Resistor_SMD:R_0603_1608Metric")
      (fields
        (field (name "MANUFACTURER PART NUMBER") "FRC0603J103TS")
        (field (name "MANUFACTURER") "FOJAN")
        (field (name "PACKAGE") "R_0603")
      )
      (libsource (lib "Device") (part "R_US"))
    )
    (comp (ref "R83")
      (value "10K")
      (footprint "Resistor_SMD:R_0603_1608Metric")
      (fields
        (field (name "MANUFACTURER PART NUMBER") "FRC0603J103TS")
        (field (name "MANUFACTURER") "FOJAN")
        (field (name "PACKAGE") "R_0603")
      )
      (libsource (lib "Device") (part "R_US"))
    )
    (comp (ref "R91")
      (value "1K")
      (footprint "Resistor_SMD:R_0603_1608Metric")
      (fields
        (field (name "MANUFACTURER PART NUMBER") "RC0603JR-071KL")
        (field (name "MANUFACTURER") "YAGEO")
        (field (name "PACKAGE") "R_0603")
      )
      (libsource (lib "Device") (part "R_US"))
    )
    (comp (ref "R92")
      (value "1K")
      (footprint "Resistor_SMD:R_0603_1608Metric")
      (fields
        (field (name "MANUFACTURER PART NUMBER") "RC0603JR-071KL")
        (field (name "MANUFACTURER") "YAGEO")
        (field (name "PACKAGE") "R_0603")
      )
      (libsource (lib "Device") (part "R_US"))
    )
    (comp (ref "R93")
      (value "1K")
      (footprint "Resistor_SMD:R_0603_1608Metric")
      (fields
        (field (name "MANUFACTURER PART NUMBER") "RC0603JR-071KL")
        (field (name "MANUFACTURER") "YAGEO")
        (field (name "PACKAGE") "R_0603")
      )
      (libsource (lib "Device") (part "R_US"))
    )
    (comp (ref "R94")
      (value "1K")
      (footprint "Resistor_SMD:R_0603_1608Metric")
      (fields
        (field (name "MANUFACTURER PART NUMBER") "RC0603JR-071KL")
        (field (name "MANUFACTURER") "YAGEO")
        (field (name "PACKAGE") "R_0603")
      )
      (libsource (lib "Device") (part "R_US"))
    )
    (comp (ref "R95")
      (value "10K")
      (footprint "Resistor_SMD:R_0603_1608Metric")
      (fields
        (field (name "MANUFACTURER PART NUMBER") "FRC0603J103TS")
        (field (name "MANUFACTURER") "FOJAN")
        (field (name "PACKAGE") "R_0603")
      )
      (libsource (lib "Device") (part "R_US"))
    )
    (comp (ref "R96")
      (value "10K")
      (footprint "Resistor_SMD:R_0603_1608Metric")
      (fields
        (field (name "MANUFACTURER PART NUMBER") "FRC0603J103TS")
        (field (name "MANUFACTURER") "FOJAN")
        (field (name "PACKAGE") "R_0603")
      )
      (libsource (lib "Device") (part "R_US"))
    )
    (comp (ref "R97")
      (value "10K")
      (footprint "Resistor_SMD:R_0603_1608Metric")
      (fields
        (field (name "MANUFACTURER PART NUMBER") "FRC0603J103TS")
        (field (name "MANUFACTURER") "FOJAN")
        (field (name "PACKAGE") "R_0603")
      )
      (libsource (lib "Device") (part "R_US"))
    )
    (comp (ref "R98")
      (value "10K")
      (footprint "Resistor_SMD:R_0603_1608Metric")
      (fields
        (field (name "MANUFACTURER PART NUMBER") "FRC0603J103TS")
        (field (name "MANUFACTURER") "FOJAN")
        (field (name "PACKAGE") "R_0603")
      )
      (libsource (lib "Device") (part "R_US"))
    )
    (comp (ref "R99")
      (value "1K")
      (footprint "Resistor_SMD:R_0603_1608Metric")
      (fields
        (field (name "MANUFACTURER PART NUMBER") "RC0603JR-071KL")
        (field (name "MANUFACTURER") "YAGEO")
        (field (name "PACKAGE") "R_0603")
      )
      (libsource (lib "Device") (part "R_US"))
    )
    (comp (ref "R100")
      (value "1K")
      (footprint "Resistor_SMD:R_0603_1608Metric")
      (fields
        (field (name "MANUFACTURER PART NUMBER") "RC0603JR-071KL")
        (field (name "MANUFACTURER") "YAGEO")
        (field (name "PACKAGE") "R_0603")
      )
      (libsource (lib "Device") (part "R_US"))
    )
    (comp (ref "R101")
      (value "10K")
      (footprint "Resistor_SMD:R_0603_1608Metric")
      (fields
        (field (name "MANUFACTURER PART NUMBER") "FRC0603J103TS")
        (field (name "MANUFACTURER") "FOJAN")
        (field (name "PACKAGE") "R_0603")
      )
      (libsource (lib "Device") (part "R_US"))
    )
    (comp (ref "R102")
      (value "10K")
      (footprint "Resistor_SMD:R_0603_1608Metric")
      (fields
        (field (name "MANUFACTURER PART NUMBER") "FRC0603J103TS")
        (field (name "MANUFACTURER") "FOJAN")
        (field (name "PACKAGE") "R_0603")
      )
      (libsource (lib "Device") (part "R_US"))
    )
    (comp (ref "R103")
      (value "1K")
      (footprint "Resistor_SMD:R_0603_1608Metric")
      (fields
        (field (name "MANUFACTURER PART NUMBER") "RC0603JR-071KL")
        (field (name "MANUFACTURER") "YAGEO")
        (field (name "PACKAGE") "R_0603")
      )
      (libsource (lib "Device") (part "R_US"))
    )
    (comp (ref "R104")
      (value "1K")
      (footprint "Resistor_SMD:R_0603_1608Metric")
      (fields
        (field (name "MANUFACTURER PART NUMBER") "RC0603JR-071KL")
        (field (name "MANUFACTURER") "YAGEO")
        (field (name "PACKAGE") "R_0603")
      )
      (libsource (lib "Device") (part "R_US"))
    )
    (comp (ref "R105")
      (value "10K")
      (footprint "Resistor_SMD:R_0603_1608Metric")
      (fields
        (field (name "MANUFACTURER PART NUMBER") "FRC0603J103TS")
        (field (name "MANUFACTURER") "FOJAN")
        (field (name "PACKAGE") "R_0603")
      )
      (libsource (lib "Device") (part "R_US"))
    )
    (comp (ref "R106")
      (value "10K")
      (footprint "Resistor_SMD:R_0603_1608Metric")
      (fields
        (field (name "MANUFACTURER PART NUMBER") "FRC0603J103TS")
        (field (name "MANUFACTURER") "FOJAN")
        (field (name "PACKAGE") "R_0603")
      )
      (libsource (lib "Device") (part "R_US"))
    )
    (comp (ref "R107")
      (value "1K")
      (footprint "Resistor_SMD:R_0603_1608Metric")
      (fields
        (field (name "MANUFACTURER PART NUMBER") "RC0603JR-071KL")
        (field (name "MANUFACTURER") "YAGEO")
        (field (name "PACKAGE") "R_0603")
      )
      (libsource (lib "Device") (part "R_US"))
    )
    (comp (ref "R108")
      (value "1K")
      (footprint "Resistor_SMD:R_0603_1608Metric")
      (fields
        (field (name "MANUFACTURER PART NUMBER") "RC0603JR-071KL")
        (field (name "MANUFACTURER") "YAGEO")
        (field (name "PACKAGE") "R_0603")
      )
      (libsource (lib "Device") (part "R_US"))
    )
    (comp (ref "R109")
      (value "10K")
      (footprint "Resistor_SMD:R_0603_1608Metric")
      (fields
        (field (name "MANUFACTURER PART NUMBER") "FRC0603J103TS")
        (field (name "MANUFACTURER") "FOJAN")
        (field (name "PACKAGE") "R_0603")
      )
      (libsource (lib "Device") (part "R_US"))
    )
    (comp (ref "R110")
      (value "10K")
      (footprint "Resistor_SMD:R_0603_1608Metric")
      (fields
        (field (name "MANUFACTURER PART NUMBER") "FRC0603J103TS")
        (field (name "MANUFACTURER") "FOJAN")
        (field (name "PACKAGE") "R_0603")
      )
      (libsource (lib "Device") (part "R_US"))
    )
    (comp (ref "R111")
      (value "1K")
      (footprint "Resistor_SMD:R_0603_1608Metric")
      (fields
        (field (name "MANUFACTURER PART NUMBER") "RC0603JR-071KL")
        (field (name "MANUFACTURER") "YAGEO")
        (field (name "PACKAGE") "R_0603")
      )
      (libsource (lib "Device") (part "R_US"))
    )
    (comp (ref "R112")
      (value "1K")
      (footprint "Resistor_SMD:R_0603_1608Metric")
      (fields
        (field (name "MANUFACTURER PART NUMBER") "RC0603JR-071KL")
        (field (name "MANUFACTURER") "YAGEO")
        (field (name "PACKAGE") "R_0603")
      )
      (libsource (lib "Device") (part "R_US"))
    )
    (comp (ref "R113")
      (value "10K")
      (footprint "Resistor_SMD:R_0603_1608Metric")
      (fields
        (field (name "MANUFACTURER PART NUMBER") "FRC0603J103TS")
        (field (name "MANUFACTURER") "FOJAN")
        (field (name "PACKAGE") "R_0603")
      )
      (libsource (lib "Device") (part "R_US"))
    )
    (comp (ref "R114")
      (value "10K")
      (footprint "Resistor_SMD:R_0603_1608Metric")
      (fields
        (field (name "MANUFACTURER PART NUMBER") "FRC0603J103TS")
        (field (name "MANUFACTURER") "FOJAN")
        (field (name "PACKAGE") "R_0603")
      )
      (libsource (lib "Device") (part "R_US"))
    )
    (comp (ref "R115")
      (value "1K")
      (footprint "Resistor_SMD:R_0603_1608Metric")
      (fields
        (field (name "MANUFACTURER PART NUMBER") "RC0603JR-071KL")
        (field (name "MANUFACTURER") "YAGEO")
        (field (name "PACKAGE") "R_0603")
      )
      (libsource (lib "Device") (part "R_US"))
    )
    (comp (ref "R116")
      (value "1K")
      (footprint "Resistor_SMD:R_0603_1608Metric")
      (fields
        (field (name "MANUFACTURER PART NUMBER") "RC0603JR-071KL")
        (field (name "MANUFACTURER") "YAGEO")
        (field (name "PACKAGE") "R_0603")
      )
      (libsource (lib "Device") (part "R_US"))
    )
    (comp (ref "R117")
      (value "10K")
      (footprint "Resistor_SMD:R_0603_1608Metric")
      (fields
        (field (name "MANUFACTURER PART NUMBER") "FRC0603J103TS")
        (field (name "MANUFACTURER") "FOJAN")
        (field (name "PACKAGE") "R_0603")
      )
      (libsource (lib "Device") (part "R_US"))
    )
    (comp (ref "R118")
      (value "10K")
      (footprint "Resistor_SMD:R_0603_1608Metric")
      (fields
        (field (name "MANUFACTURER PART NUMBER") "FRC0603J103TS")
        (field (name "MANUFACTURER") "FOJAN")
        (field (name "PACKAGE") "R_0603")
      )
      (libsource (lib "Device") (part "R_US"))
    )
    (comp (ref "R119")
      (value "1K")
      (footprint "Resistor_SMD:R_0603_1608Metric")
      (fields
        (field (name "MANUFACTURER PART NUMBER") "RC0603JR-071KL")
        (field (name "MANUFACTURER") "YAGEO")
        (field (name "PACKAGE") "R_0603")
      )
      (libsource (lib "Device") (part "R_US"))
    )
    (comp (ref "R120")
      (value "1K")
      (footprint "Resistor_SMD:R_0603_1608Metric")
      (fields
        (field (name "MANUFACTURER PART NUMBER") "RC0603JR-071KL")
        (field (name "MANUFACTURER") "YAGEO")
        (field (name "PACKAGE") "R_0603")
      )
      (libsource (lib "Device") (part "R_US"))
    )
    (comp (ref "R121")
      (value "10K")
      (footprint "Resistor_SMD:R_0603_1608Metric")
      (fields
        (field (name "MANUFACTURER PART NUMBER") "FRC0603J103TS")
        (field (name "MANUFACTURER") "FOJAN")
        (field (name "PACKAGE") "R_0603")
      )
      (libsource (lib "Device") (part "R_US"))
    )
    (comp (ref "R122")
      (value "10K")
      (footprint "Resistor_SMD:R_0603_1608Metric")
      (fields
        (field (name "MANUFACTURER PART NUMBER") "FRC0603J103TS")
        (field (name "MANUFACTURER") "FOJAN")
        (field (name "PACKAGE") "R_0603")
      )
      (libsource (lib "Device") (part "R_US"))
    )
  )
  (nets
    (net (code "1") (name "+12V") (class "Default")
      (node (ref "K1") (pin "A3") (pinfunction "A3_A3") (pintype "passive"))
      (node (ref "K10") (pin "A3") (pinfunction "A3_A3") (pintype "passive"))
      (node (ref "K11") (pin "A3") (pinfunction "A3_A3") (pintype "passive"))
      (node (ref "K12") (pin "A3") (pinfunction "A3_A3") (pintype "passive"))
      (node (ref "K13") (pin "A3") (pinfunction "A3_A3") (pintype "passive"))
      (node (ref "K14") (pin "A3") (pinfunction "A3_A3") (pintype "passive"))
      (node (ref "K15") (pin "A3") (pinfunction "A3_A3") (pintype "passive"))
      (node (ref "K16") (pin "A3") (pinfunction "A3_A3") (pintype "passive"))
      (node (ref "K17") (pin "A3") (pinfunction "A3_A3") (pintype "passive"))
      (node (ref "K18") (pin "A3") (pinfunction "A3_A3") (pintype "passive"))
      (node (ref "K4") (pin "A3") (pinfunction "A3_A3") (pintype "passive"))
      (node (ref "K5") (pin "A3") (pinfunction "A3_A3") (pintype "passive"))
      (node (ref "K6") (pin "A3") (pinfunction "A3_A3") (pintype "passive"))
      (node (ref "K7") (pin "A3") (pinfunction "A3_A3") (pintype "passive"))
      (node (ref "K8") (pin "A3") (pinfunction "A3_A3") (pintype "passive"))
      (node (ref "K9") (pin "A3") (pinfunction "A3_A3") (pintype "passive"))
    )
    (net (code "2") (name "/R1_A1") (class "Default")
      (node (ref "R34") (pin "2") (pinfunction "2_2") (pintype "passive"))
    )
    (net (code "3") (name "/R1_A2") (class "Default")
      (node (ref "R33") (pin "2") (pinfunction "2_2") (pintype "passive"))
    )
    (net (code "4") (name "/R1_COM") (class "Default")
      (node (ref "K1") (pin "11") (pinfunction "11_11") (pintype "passive"))
    )
    (net (code "5") (name "/R1_NC") (class "Default")
      (node (ref "K1") (pin "12") (pinfunction "12_12") (pintype "passive"))
    )
    (net (code "6") (name "/R1_NO") (class "Default")
      (node (ref "K1") (pin "14") (pinfunction "14_14") (pintype "passive"))
    )
    (net (code "7") (name "/R2_A1") (class "Default")
      (node (ref "R57") (pin "2") (pinfunction "2_2") (pintype "passive"))
    )
    (net (code "8") (name "/R2_A2") (class "Default")
      (node (ref "R56") (pin "2") (pinfunction "2_2") (pintype "passive"))
    )
    (net (code "9") (name "/R2_COM") (class "Default")
      (node (ref "K4") (pin "11") (pinfunction "11_11") (pintype "passive"))
    )
    (net (code "10") (name "/R2_NC") (class "Default")
      (node (ref "K4") (pin "12") (pinfunction "12_12") (pintype "passive"))
    )
    (net (code "11") (name "/R2_NO") (class "Default")
      (node (ref "K4") (pin "14") (pinfunction "14_14") (pintype "passive"))
    )
    (net (code "12") (name "/R3_A1") (class "Default")
      (node (ref "R61") (pin "2") (pinfunction "2_2") (pintype "passive"))
    )
    (net (code "13") (name "/R3_A2") (class "Default")
      (node (ref "R60") (pin "2") (pinfunction "2_2") (pintype "passive"))
    )
    (net (code "14") (name "/R3_COM") (class "Default")
      (node (ref "K5") (pin "11") (pinfunction "11_11") (pintype "passive"))
    )
    (net (code "15") (name "/R3_NC") (class "Default")
      (node (ref "K5") (pin "12") (pinfunction "12_12") (pintype "passive"))
    )
    (net (code "16") (name "/R3_NO") (class "Default")
      (node (ref "K5") (pin "14") (pinfunction "14_14") (pintype "passive"))
    )
    (net (code "17") (name "/R4_A1") (class "Default")
      (node (ref "R65") (pin "2") (pinfunction "2_2") (pintype "passive"))
    )
    (net (code "18") (name "/R4_A2") (class "Default")
      (node (ref "R64") (pin "2") (pinfunction "2_2") (pintype "passive"))
    )
    (net (code "19") (name "/R4_COM") (class "Default")
      (node (ref "K6") (pin "11") (pinfunction "11_11") (pintype "passive"))
    )
    (net (code "20") (name "/R4_NC") (class "Default")
      (node (ref "K6") (pin "12") (pinfunction "12_12") (pintype "passive"))
    )
    (net (code "21") (name "/R4_NO") (class "Default")
      (node (ref "K6") (pin "14") (pinfunction "14_14") (pintype "passive"))
    )
    (net (code "22") (name "/R5_A1") (class "Default")
      (node (ref "R69") (pin "2") (pinfunction "2_2") (pintype "passive"))
    )
    (net (code "23") (name "/R5_A2") (class "Default")
      (node (ref "R68") (pin "2") (pinfunction "2_2") (pintype "passive"))
    )
    (net (code "24") (name "/R5_COM") (class "Default")
      (node (ref "K7") (pin "11") (pinfunction "11_11") (pintype "passive"))
    )
    (net (code "25") (name "/R5_NC") (class "Default")
      (node (ref "K7") (pin "12") (pinfunction "12_12") (pintype "passive"))
    )
    (net (code "26") (name "/R5_NO") (class "Default")
      (node (ref "K7") (pin "14") (pinfunction "14_14") (pintype "passive"))
    )
    (net (code "27") (name "/R6_A1") (class "Default")
      (node (ref "R73") (pin "2") (pinfunction "2_2") (pintype "passive"))
    )
    (net (code "28") (name "/R6_A2") (class "Default")
      (node (ref "R72") (pin "2") (pinfunction "2_2") (pintype "passive"))
    )
    (net (code "29") (name "/R6_COM") (class "Default")
      (node (ref "K8") (pin "11") (pinfunction "11_11") (pintype "passive"))
    )
    (net (code "30") (name "/R6_NC") (class "Default")
      (node (ref "K8") (pin "12") (pinfunction "12_12") (pintype "passive"))
    )
    (net (code "31") (name "/R6_NO") (class "Default")
      (node (ref "K8") (pin "14") (pinfunction "14_14") (pintype "passive"))
    )
    (net (code "32") (name "/R7_A1") (class "Default")
      (node (ref "R77") (pin "2") (pinfunction "2_2") (pintype "passive"))
    )
    (net (code "33") (name "/R7_A2") (class "Default")
      (node (ref "R76") (pin "2") (pinfunction "2_2") (pintype "passive"))
    )
    (net (code "34") (name "/R7_COM") (class "Default")
      (node (ref "K9") (pin "11") (pinfunction "11_11") (pintype "passive"))
    )
    (net (code "35") (name "/R7_NC") (class "Default")
      (node (ref "K9") (pin "12") (pinfunction "12_12") (pintype "passive"))
    )
    (net (code "36") (name "/R7_NO") (class "Default")
      (node (ref "K9") (pin "14") (pinfunction "14_14") (pintype "passive"))
    )
    (net (code "37") (name "/R8_A1") (class "Default")
      (node (ref "R81") (pin "2") (pinfunction "2_2") (pintype "passive"))
    )
    (net (code "38") (name "/R8_A2") (class "Default")
      (node (ref "R80") (pin "2") (pinfunction "2_2") (pintype "passive"))
    )
    (net (code "39") (name "/R8_COM") (class "Default")
      (node (ref "K10") (pin "11") (pinfunction "11_11") (pintype "passive"))
    )
    (net (code "40") (name "/R8_NC") (class "Default")
      (node (ref "K10") (pin "12") (pinfunction "12_12") (pintype "passive"))
    )
    (net (code "41") (name "/R8_NO") (class "Default")
      (node (ref "K10") (pin "14") (pinfunction "14_14") (pintype "passive"))
    )
    (net (code "42") (name "/R9_A1") (class "Default")
      (node (ref "R93") (pin "2") (pinfunction "2_2") (pintype "passive"))
    )
    (net (code "43") (name "/R9_A2") (class "Default")
      (node (ref "R91") (pin "2") (pinfunction "2_2") (pintype "passive"))
    )
    (net (code "44") (name "/R9_COM") (class "Default")
      (node (ref "K11") (pin "11") (pinfunction "11_11") (pintype "passive"))
    )
    (net (code "45") (name "/R9_NC") (class "Default")
      (node (ref "K11") (pin "12") (pinfunction "12_12") (pintype "passive"))
    )
    (net (code "46") (name "/R9_NO") (class "Default")
      (node (ref "K11") (pin "14") (pinfunction "14_14") (pintype "passive"))
    )
    (net (code "47") (name "/R10_A1") (class "Default")
      (node (ref "R94") (pin "2") (pinfunction "2_2") (pintype "passive"))
    )
    (net (code "48") (name "/R10_A2") (class "Default")
      (node (ref "R92") (pin "2") (pinfunction "2_2") (pintype "passive"))
    )
    (net (code "49") (name "/R10_COM") (class "Default")
      (node (ref "K12") (pin "11") (pinfunction "11_11") (pintype "passive"))
    )
    (net (code "50") (name "/R10_NC") (class "Default")
      (node (ref "K12") (pin "12") (pinfunction "12_12") (pintype "passive"))
    )
    (net (code "51") (name "/R10_NO") (class "Default")
      (node (ref "K12") (pin "14") (pinfunction "14_14") (pintype "passive"))
    )
    (net (code "52") (name "/R11_A1") (class "Default")
      (node (ref "R100") (pin "2") (pinfunction "2_2") (pintype "passive"))
    )
    (net (code "53") (name "/R11_A2") (class "Default")
      (node (ref "R99") (pin "2") (pinfunction "2_2") (pintype "passive"))
    )
    (net (code "54") (name "/R11_COM") (class "Default")
      (node (ref "K13") (pin "11") (pinfunction "11_11") (pintype "passive"))
    )
    (net (code "55") (name "/R11_NC") (class "Default")
      (node (ref "K13") (pin "12") (pinfunction "12_12") (pintype "passive"))
    )
    (net (code "56") (name "/R11_NO") (class "Default")
      (node (ref "K13") (pin "14") (pinfunction "14_14") (pintype "passive"))
    )
    (net (code "57") (name "/R12_A1") (class "Default")
      (node (ref "R104") (pin "2") (pinfunction "2_2") (pintype "passive"))
    )
    (net (code "58") (name "/R12_A2") (class "Default")
      (node (ref "R103") (pin "2") (pinfunction "2_2") (pintype "passive"))
    )
    (net (code "59") (name "/R12_COM") (class "Default")
      (node (ref "K14") (pin "11") (pinfunction "11_11") (pintype "passive"))
    )
    (net (code "60") (name "/R12_NC") (class "Default")
      (node (ref "K14") (pin "12") (pinfunction "12_12") (pintype "passive"))
    )
    (net (code "61") (name "/R12_NO") (class "Default")
      (node (ref "K14") (pin "14") (pinfunction "14_14") (pintype "passive"))
    )
    (net (code "62") (name "/R13_A1") (class "Default")
      (node (ref "R108") (pin "2") (pinfunction "2_2") (pintype "passive"))
    )
    (net (code "63") (name "/R13_A2") (class "Default")
      (node (ref "R107") (pin "2") (pinfunction "2_2") (pintype "passive"))
    )
    (net (code "64") (name "/R13_COM") (class "Default")
      (node (ref "K15") (pin "11") (pinfunction "11_11") (pintype "passive"))
    )
    (net (code "65") (name "/R13_NC") (class "Default")
      (node (ref "K15") (pin "12") (pinfunction "12_12") (pintype "passive"))
    )
    (net (code "66") (name "/R13_NO") (class "Default")
      (node (ref "K15") (pin "14") (pinfunction "14_14") (pintype "passive"))
    )
    (net (code "67") (name "/R14_A1") (class "Default")
      (node (ref "R112") (pin "2") (pinfunction "2_2") (pintype "passive"))
    )
    (net (code "68") (name "/R14_A2") (class "Default")
      (node (ref "R111") (pin "2") (pinfunction "2_2") (pintype "passive"))
    )
    (net (code "69") (name "/R14_COM") (class "Default")
      (node (ref "K16") (pin "11") (pinfunction "11_11") (pintype "passive"))
    )
    (net (code "70") (name "/R14_NC") (class "Default")
      (node (ref "K16") (pin "12") (pinfunction "12_12") (pintype "passive"))
    )
    (net (code "71") (name "/R14_NO") (class "Default")
      (node (ref "K16") (pin "14") (pinfunction "14_14") (pintype "passive"))
    )
    (net (code "72") (name "/R15_A1") (class "Default")
      (node (ref "R116") (pin "2") (pinfunction "2_2") (pintype "passive"))
    )
    (net (code "73") (name "/R15_A2") (class "Default")
      (node (ref "R115") (pin "2") (pinfunction "2_2") (pintype "passive"))
    )
    (net (code "74") (name "/R15_COM") (class "Default")
      (node (ref "K17") (pin "11") (pinfunction "11_11") (pintype "passive"))
    )
    (net (code "75") (name "/R15_NC") (class "Default")
      (node (ref "K17") (pin "12") (pinfunction "12_12") (pintype "passive"))
    )
    (net (code "76") (name "/R15_NO") (class "Default")
      (node (ref "K17") (pin "14") (pinfunction "14_14") (pintype "passive"))
    )
    (net (code "77") (name "/R16_A1") (class "Default")
      (node (ref "R120") (pin "2") (pinfunction "2_2") (pintype "passive"))
    )
    (net (code "78") (name "/R16_A2") (class "Default")
      (node (ref "R119") (pin "2") (pinfunction "2_2") (pintype "passive"))
    )
    (net (code "79") (name "/R16_COM") (class "Default")
      (node (ref "K18") (pin "11") (pinfunction "11_11") (pintype "passive"))
    )
    (net (code "80") (name "/R16_NC") (class "Default")
      (node (ref "K18") (pin "12") (pinfunction "12_12") (pintype "passive"))
    )
    (net (code "81") (name "/R16_NO") (class "Default")
      (node (ref "K18") (pin "14") (pinfunction "14_14") (pintype "passive"))
    )
    (net (code "82") (name "GND") (class "Default")
      (node (ref "C12") (pin "1") (pinfunction "1_1") (pintype "passive"))
      (node (ref "C13") (pin "1") (pinfunction "1_1") (pintype "passive"))
      (node (ref "C14") (pin "1") (pinfunction "1_1") (pintype "passive"))
      (node (ref "C15") (pin "1") (pinfunction "1_1") (pintype "passive"))
      (node (ref "C16") (pin "1") (pinfunction "1_1") (pintype "passive"))
      (node (ref "C17") (pin "1") (pinfunction "1_1") (pintype "passive"))
      (node (ref "C18") (pin "1") (pinfunction "1_1") (pintype "passive"))
      (node (ref "C19") (pin "1") (pinfunction "1_1") (pintype "passive"))
      (node (ref "C20") (pin "1") (pinfunction "1_1") (pintype "passive"))
      (node (ref "C21") (pin "1") (pinfunction "1_1") (pintype "passive"))
      (node (ref "C22") (pin "1") (pinfunction "1_1") (pintype "passive"))
      (node (ref "C23") (pin "1") (pinfunction "1_1") (pintype "passive"))
      (node (ref "C24") (pin "1") (pinfunction "1_1") (pintype "passive"))
      (node (ref "C25") (pin "1") (pinfunction "1_1") (pintype "passive"))
      (node (ref "C26") (pin "1") (pinfunction "1_1") (pintype "passive"))
      (node (ref "C27") (pin "1") (pinfunction "1_1") (pintype "passive"))
      (node (ref "C28") (pin "1") (pinfunction "1_1") (pintype "passive"))
      (node (ref "C29") (pin "1") (pinfunction "1_1") (pintype "passive"))
      (node (ref "C30") (pin "1") (pinfunction "1_1") (pintype "passive"))
      (node (ref "C31") (pin "1") (pinfunction "1_1") (pintype "passive"))
      (node (ref "C32") (pin "1") (pinfunction "1_1") (pintype "passive"))
      (node (ref "C37") (pin "1") (pinfunction "1_1") (pintype "passive"))
      (node (ref "C38") (pin "1") (pinfunction "1_1") (pintype "passive"))
      (node (ref "C39") (pin "1") (pinfunction "1_1") (pintype "passive"))
      (node (ref "C40") (pin "1") (pinfunction "1_1") (pintype "passive"))
      (node (ref "C41") (pin "1") (pinfunction "1_1") (pintype "passive"))
      (node (ref "C42") (pin "1") (pinfunction "1_1") (pintype "passive"))
      (node (ref "C43") (pin "1") (pinfunction "1_1") (pintype "passive"))
      (node (ref "C44") (pin "1") (pinfunction "1_1") (pintype "passive"))
      (node (ref "C45") (pin "1") (pinfunction "1_1") (pintype "passive"))
      (node (ref "C6") (pin "1") (pinfunction "1_1") (pintype "passive"))
      (node (ref "C7") (pin "1") (pinfunction "1_1") (pintype "passive"))
      (node (ref "Q18") (pin "2") (pinfunction "S_2") (pintype "passive"))
      (node (ref "Q19") (pin "2") (pinfunction "S_2") (pintype "passive"))
      (node (ref "Q20") (pin "2") (pinfunction "S_2") (pintype "passive"))
      (node (ref "Q21") (pin "2") (pinfunction "S_2") (pintype "passive"))
      (node (ref "Q22") (pin "2") (pinfunction "S_2") (pintype "passive"))
      (node (ref "Q23") (pin "2") (pinfunction "S_2") (pintype "passive"))
      (node (ref "Q24") (pin "2") (pinfunction "S_2") (pintype "passive"))
      (node (ref "Q25") (pin "2") (pinfunction "S_2") (pintype "passive"))
      (node (ref "Q26") (pin "2") (pinfunction "S_2") (pintype "passive"))
      (node (ref "Q27") (pin "2") (pinfunction "S_2") (pintype "passive"))
      (node (ref "Q28") (pin "2") (pinfunction "S_2") (pintype "passive"))
      (node (ref "Q29") (pin "2") (pinfunction "S_2") (pintype "passive"))
      (node (ref "Q3") (pin "2") (pinfunction "S_2") (pintype "passive"))
      (node (ref "Q30") (pin "2") (pinfunction "S_2") (pintype "passive"))
      (node (ref "Q31") (pin "2") (pinfunction "S_2") (pintype "passive"))
      (node (ref "Q33") (pin "2") (pinfunction "S_2") (pintype "passive"))
      (node (ref "Q34") (pin "2") (pinfunction "S_2") (pintype "passive"))
      (node (ref "Q35") (pin "2") (pinfunction "S_2") (pintype "passive"))
      (node (ref "Q36") (pin "2") (pinfunction "S_2") (pintype "passive"))
      (node (ref "Q37") (pin "2") (pinfunction "S_2") (pintype "passive"))
      (node (ref "Q38") (pin "2") (pinfunction "S_2") (pintype "passive"))
      (node (ref "Q39") (pin "2") (pinfunction "S_2") (pintype "passive"))
      (node (ref "Q4") (pin "2") (pinfunction "S_2") (pintype "passive"))
      (node (ref "Q40") (pin "2") (pinfunction "S_2") (pintype "passive"))
      (node (ref "Q41") (pin "2") (pinfunction "S_2") (pintype "passive"))
      (node (ref "Q42") (pin "2") (pinfunction "S_2") (pintype "passive"))
      (node (ref "Q43") (pin "2") (pinfunction "S_2") (pintype "passive"))
      (node (ref "Q44") (pin "2") (pinfunction "S_2") (pintype "passive"))
      (node (ref "Q45") (pin "2") (pinfunction "S_2") (pintype "passive"))
      (node (ref "Q46") (pin "2") (pinfunction "S_2") (pintype "passive"))
      (node (ref "Q47") (pin "2") (pinfunction "S_2") (pintype "passive"))
      (node (ref "Q48") (pin "2") (pinfunction "S_2") (pintype "passive"))
      (node (ref "R101") (pin "1") (pinfunction "1_1") (pintype "passive"))
      (node (ref "R102") (pin "1") (pinfunction "1_1") (pintype "passive"))
      (node (ref "R105") (pin "1") (pinfunction "1_1") (pintype "passive"))
      (node (ref "R106") (pin "1") (pinfunction "1_1") (pintype "passive"))
      (node (ref "R109") (pin "1") (pinfunction "1_1") (pintype "passive"))
      (node (ref "R110") (pin "1") (pinfunction "1_1") (pintype "passive"))
      (node (ref "R113") (pin "1") (pinfunction "1_1") (pintype "passive"))
      (node (ref "R114") (pin "1") (pinfunction "1_1") (pintype "passive"))
      (node (ref "R117") (pin "1") (pinfunction "1_1") (pintype "passive"))
      (node (ref "R118") (pin "1") (pinfunction "1_1") (pintype "passive"))
      (node (ref "R121") (pin "1") (pinfunction "1_1") (pintype "passive"))
      (node (ref "R122") (pin "1") (pinfunction "1_1") (pintype "passive"))
      (node (ref "R32") (pin "1") (pinfunction "1_1") (pintype "passive"))
      (node (ref "R35") (pin "1") (pinfunction "1_1") (pintype "passive"))
      (node (ref "R58") (pin "1") (pinfunction "1_1") (pintype "passive"))
      (node (ref "R59") (pin "1") (pinfunction "1_1") (pintype "passive"))
      (node (ref "R62") (pin "1") (pinfunction "1_1") (pintype "passive"))
      (node (ref "R63") (pin "1") (pinfunction "1_1") (pintype "passive"))
      (node (ref "R66") (pin "1") (pinfunction "1_1") (pintype "passive"))
      (node (ref "R67") (pin "1") (pinfunction "1_1") (pintype "passive"))
      (node (ref "R70") (pin "1") (pinfunction "1_1") (pintype "passive"))
      (node (ref "R71") (pin "1") (pinfunction "1_1") (pintype "passive"))
      (node (ref "R74") (pin "1") (pinfunction "1_1") (pintype "passive"))
      (node (ref "R75") (pin "1") (pinfunction "1_1") (pintype "passive"))
      (node (ref "R78") (pin "1") (pinfunction "1_1") (pintype "passive"))
      (node (ref "R79") (pin "1") (pinfunction "1_1") (pintype "passive"))
      (node (ref "R82") (pin "1") (pinfunction "1_1") (pintype "passive"))
      (node (ref "R83") (pin "1") (pinfunction "1_1") (pintype "passive"))
      (node (ref "R95") (pin "1") (pinfunction "1_1") (pintype "passive"))
      (node (ref "R96") (pin "1") (pinfunction "1_1") (pintype "passive"))
      (node (ref "R97") (pin "1") (pinfunction "1_1") (pintype "passive"))
      (node (ref "R98") (pin "1") (pinfunction "1_1") (pintype "passive"))
    )
    (net (code "83") (name "Net-(Q3-D)") (class "Default")
      (node (ref "K1") (pin "A2") (pinfunction "A2_A2") (pintype "passive"))
      (node (ref "Q3") (pin "3") (pinfunction "D_3") (pintype "passive"))
    )
    (net (code "84") (name "Net-(Q3-G)") (class "Default")
      (node (ref "C6") (pin "2") (pinfunction "2_2") (pintype "passive"))
      (node (ref "Q3") (pin "1") (pinfunction "G_1") (pintype "passive"))
      (node (ref "R32") (pin "2") (pinfunction "2_2") (pintype "passive"))
      (node (ref "R33") (pin "1") (pinfunction "1_1") (pintype "passive"))
    )
    (net (code "85") (name "Net-(Q4-D)") (class "Default")
      (node (ref "K1") (pin "A1") (pinfunction "A1_A1") (pintype "passive"))
      (node (ref "Q4") (pin "3") (pinfunction "D_3") (pintype "passive"))
    )
    (net (code "86") (name "Net-(Q4-G)") (class "Default")
      (node (ref "C7") (pin "2") (pinfunction "2_2") (pintype "passive"))
      (node (ref "Q4") (pin "1") (pinfunction "G_1") (pintype "passive"))
      (node (ref "R34") (pin "1") (pinfunction "1_1") (pintype "passive"))
      (node (ref "R35") (pin "2") (pinfunction "2_2") (pintype "passive"))
    )
    (net (code "87") (name "Net-(Q18-D)") (class "Default")
      (node (ref "K4") (pin "A1") (pinfunction "A1_A1") (pintype "passive"))
      (node (ref "Q18") (pin "3") (pinfunction "D_3") (pintype "passive"))
    )
    (net (code "88") (name "Net-(Q18-G)") (class "Default")
      (node (ref "C12") (pin "2") (pinfunction "2_2") (pintype "passive"))
      (node (ref "Q18") (pin "1") (pinfunction "G_1") (pintype "passive"))
      (node (ref "R57") (pin "1") (pinfunction "1_1") (pintype "passive"))
      (node (ref "R58") (pin "2") (pinfunction "2_2") (pintype "passive"))
    )
    (net (code "89") (name "Net-(Q19-D)") (class "Default")
      (node (ref "K4") (pin "A2") (pinfunction "A2_A2") (pintype "passive"))
      (node (ref "Q19") (pin "3") (pinfunction "D_3") (pintype "passive"))
    )
    (net (code "90") (name "Net-(Q19-G)") (class "Default")
      (node (ref "C13") (pin "2") (pinfunction "2_2") (pintype "passive"))
      (node (ref "Q19") (pin "1") (pinfunction "G_1") (pintype "passive"))
      (node (ref "R56") (pin "1") (pinfunction "1_1") (pintype "passive"))
      (node (ref "R59") (pin "2") (pinfunction "2_2") (pintype "passive"))
    )
    (net (code "91") (name "Net-(Q20-D)") (class "Default")
      (node (ref "K5") (pin "A1") (pinfunction "A1_A1") (pintype "passive"))
      (node (ref "Q20") (pin "3") (pinfunction "D_3") (pintype "passive"))
    )
    (net (code "92") (name "Net-(Q20-G)") (class "Default")
      (node (ref "C14") (pin "2") (pinfunction "2_2") (pintype "passive"))
      (node (ref "Q20") (pin "1") (pinfunction "G_1") (pintype "passive"))
      (node (ref "R61") (pin "1") (pinfunction "1_1") (pintype "passive"))
      (node (ref "R62") (pin "2") (pinfunction "2_2") (pintype "passive"))
    )
    (net (code "93") (name "Net-(Q21-D)") (class "Default")
      (node (ref "K5") (pin "A2") (pinfunction "A2_A2") (pintype "passive"))
      (node (ref "Q21") (pin "3") (pinfunction "D_3") (pintype "passive"))
    )
    (net (code "94") (name "Net-(Q21-G)") (class "Default")
      (node (ref "C15") (pin "2") (pinfunction "2_2") (pintype "passive"))
      (node (ref "Q21") (pin "1") (pinfunction "G_1") (pintype "passive"))
      (node (ref "R60") (pin "1") (pinfunction "1_1") (pintype "passive"))
      (node (ref "R63") (pin "2") (pinfunction "2_2") (pintype "passive"))
    )
    (net (code "95") (name "Net-(Q22-D)") (class "Default")
      (node (ref "K6") (pin "A1") (pinfunction "A1_A1") (pintype "passive"))
      (node (ref "Q22") (pin "3") (pinfunction "D_3") (pintype "passive"))
    )
    (net (code "96") (name "Net-(Q22-G)") (class "Default")
      (node (ref "C16") (pin "2") (pinfunction "2_2") (pintype "passive"))
      (node (ref "Q22") (pin "1") (pinfunction "G_1") (pintype "passive"))
      (node (ref "R65") (pin "1") (pinfunction "1_1") (pintype "passive"))
      (node (ref "R66") (pin "2") (pinfunction "2_2") (pintype "passive"))
    )
    (net (code "97") (name "Net-(Q23-D)") (class "Default")
      (node (ref "K6") (pin "A2") (pinfunction "A2_A2") (pintype "passive"))
      (node (ref "Q23") (pin "3") (pinfunction "D_3") (pintype "passive"))
    )
    (net (code "98") (name "Net-(Q23-G)") (class "Default")
      (node (ref "C17") (pin "2") (pinfunction "2_2") (pintype "passive"))
      (node (ref "Q23") (pin "1") (pinfunction "G_1") (pintype "passive"))
      (node (ref "R64") (pin "1") (pinfunction "1_1") (pintype "passive"))
      (node (ref "R67") (pin "2") (pinfunction "2_2") (pintype "passive"))
    )
    (net (code "99") (name "Net-(Q24-D)") (class "Default")
      (node (ref "K7") (pin "A1") (pinfunction "A1_A1") (pintype "passive"))
      (node (ref "Q24") (pin "3") (pinfunction "D_3") (pintype "passive"))
    )
    (net (code "100") (name "Net-(Q24-G)") (class "Default")
      (node (ref "C18") (pin "2") (pinfunction "2_2") (pintype "passive"))
      (node (ref "Q24") (pin "1") (pinfunction "G_1") (pintype "passive"))
      (node (ref "R69") (pin "1") (pinfunction "1_1") (pintype "passive"))
      (node (ref "R70") (pin "2") (pinfunction "2_2") (pintype "passive"))
    )
    (net (code "101") (name "Net-(Q25-D)") (class "Default")
      (node (ref "K7") (pin "A2") (pinfunction "A2_A2") (pintype "passive"))
      (node (ref "Q25") (pin "3") (pinfunction "D_3") (pintype "passive"))
    )
    (net (code "102") (name "Net-(Q25-G)") (class "Default")
      (node (ref "C19") (pin "2") (pinfunction "2_2") (pintype "passive"))
      (node (ref "Q25") (pin "1") (pinfunction "G_1") (pintype "passive"))
      (node (ref "R68") (pin "1") (pinfunction "1_1") (pintype "passive"))
      (node (ref "R71") (pin "2") (pinfunction "2_2") (pintype "passive"))
    )
    (net (code "103") (name "Net-(Q26-D)") (class "Default")
      (node (ref "K8") (pin "A1") (pinfunction "A1_A1") (pintype "passive"))
      (node (ref "Q26") (pin "3") (pinfunction "D_3") (pintype "passive"))
    )
    (net (code "104") (name "Net-(Q26-G)") (class "Default")
      (node (ref "C20") (pin "2") (pinfunction "2_2") (pintype "passive"))
      (node (ref "Q26") (pin "1") (pinfunction "G_1") (pintype "passive"))
      (node (ref "R73") (pin "1") (pinfunction "1_1") (pintype "passive"))
      (node (ref "R74") (pin "2") (pinfunction "2_2") (pintype "passive"))
    )
    (net (code "105") (name "Net-(Q27-D)") (class "Default")
      (node (ref "K8") (pin "A2") (pinfunction "A2_A2") (pintype "passive"))
      (node (ref "Q27") (pin "3") (pinfunction "D_3") (pintype "passive"))
    )
    (net (code "106") (name "Net-(Q27-G)") (class "Default")
      (node (ref "C21") (pin "2") (pinfunction "2_2") (pintype "passive"))
      (node (ref "Q27") (pin "1") (pinfunction "G_1") (pintype "passive"))
      (node (ref "R72") (pin "1") (pinfunction "1_1") (pintype "passive"))
      (node (ref "R75") (pin "2") (pinfunction "2_2") (pintype "passive"))
    )
    (net (code "107") (name "Net-(Q28-D)") (class "Default")
      (node (ref "K9") (pin "A1") (pinfunction "A1_A1") (pintype "passive"))
      (node (ref "Q28") (pin "3") (pinfunction "D_3") (pintype "passive"))
    )
    (net (code "108") (name "Net-(Q28-G)") (class "Default")
      (node (ref "C22") (pin "2") (pinfunction "2_2") (pintype "passive"))
      (node (ref "Q28") (pin "1") (pinfunction "G_1") (pintype "passive"))
      (node (ref "R77") (pin "1") (pinfunction "1_1") (pintype "passive"))
      (node (ref "R78") (pin "2") (pinfunction "2_2") (pintype "passive"))
    )
    (net (code "109") (name "Net-(Q29-D)") (class "Default")
      (node (ref "K9") (pin "A2") (pinfunction "A2_A2") (pintype "passive"))
      (node (ref "Q29") (pin "3") (pinfunction "D_3") (pintype "passive"))
    )
    (net (code "110") (name "Net-(Q29-G)") (class "Default")
      (node (ref "C23") (pin "2") (pinfunction "2_2") (pintype "passive"))
      (node (ref "Q29") (pin "1") (pinfunction "G_1") (pintype "passive"))
      (node (ref "R76") (pin "1") (pinfunction "1_1") (pintype "passive"))
      (node (ref "R79") (pin "2") (pinfunction "2_2") (pintype "passive"))
    )
    (net (code "111") (name "Net-(Q30-D)") (class "Default")
      (node (ref "K10") (pin "A1") (pinfunction "A1_A1") (pintype "passive"))
      (node (ref "Q30") (pin "3") (pinfunction "D_3") (pintype "passive"))
    )
    (net (code "112") (name "Net-(Q30-G)") (class "Default")
      (node (ref "C24") (pin "2") (pinfunction "2_2") (pintype "passive"))
      (node (ref "Q30") (pin "1") (pinfunction "G_1") (pintype "passive"))
      (node (ref "R81") (pin "1") (pinfunction "1_1") (pintype "passive"))
      (node (ref "R82") (pin "2") (pinfunction "2_2") (pintype "passive"))
    )
    (net (code "113") (name "Net-(Q31-D)") (class "Default")
      (node (ref "K10") (pin "A2") (pinfunction "A2_A2") (pintype "passive"))
      (node (ref "Q31") (pin "3") (pinfunction "D_3") (pintype "passive"))
    )
    (net (code "114") (name "Net-(Q31-G)") (class "Default")
      (node (ref "C25") (pin "2") (pinfunction "2_2") (pintype "passive"))
      (node (ref "Q31") (pin "1") (pinfunction "G_1") (pintype "passive"))
      (node (ref "R80") (pin "1") (pinfunction "1_1") (pintype "passive"))
      (node (ref "R83") (pin "2") (pinfunction "2_2") (pintype "passive"))
    )
    (net (code "115") (name "Net-(Q33-D)") (class "Default")
      (node (ref "K11") (pin "A1") (pinfunction "A1_A1") (pintype "passive"))
      (node (ref "Q33") (pin "3") (pinfunction "D_3") (pintype "passive"))
    )
    (net (code "116") (name "Net-(Q33-G)") (class "Default")
      (node (ref "C26") (pin "2") (pinfunction "2_2") (pintype "passive"))
      (node (ref "Q33") (pin "1") (pinfunction "G_1") (pintype "passive"))
      (node (ref "R93") (pin "1") (pinfunction "1_1") (pintype "passive"))
      (node (ref "R95") (pin "2") (pinfunction "2_2") (pintype "passive"))
    )
    (net (code "117") (name "Net-(Q34-D)") (class "Default")
      (node (ref "K12") (pin "A1") (pinfunction "A1_A1") (pintype "passive"))
      (node (ref "Q34") (pin "3") (pinfunction "D_3") (pintype "passive"))
    )
    (net (code "118") (name "Net-(Q34-G)") (class "Default")
      (node (ref "C27") (pin "2") (pinfunction "2_2") (pintype "passive"))
      (node (ref "Q34") (pin "1") (pinfunction "G_1") (pintype "passive"))
      (node (ref "R94") (pin "1") (pinfunction "1_1") (pintype "passive"))
      (node (ref "R97") (pin "2") (pinfunction "2_2") (pintype "passive"))
    )
    (net (code "119") (name "Net-(Q35-D)") (class "Default")
      (node (ref "K11") (pin "A2") (pinfunction "A2_A2") (pintype "passive"))
      (node (ref "Q35") (pin "3") (pinfunction "D_3") (pintype "passive"))
    )
    (net (code "120") (name "Net-(Q35-G)") (class "Default")
      (node (ref "C28") (pin "2") (pinfunction "2_2") (pintype "passive"))
      (node (ref "Q35") (pin "1") (pinfunction "G_1") (pintype "passive"))
      (node (ref "R91") (pin "1") (pinfunction "1_1") (pintype "passive"))
      (node (ref "R96") (pin "2") (pinfunction "2_2") (pintype "passive"))
    )
    (net (code "121") (name "Net-(Q36-D)") (class "Default")
      (node (ref "K12") (pin "A2") (pinfunction "A2_A2") (pintype "passive"))
      (node (ref "Q36") (pin "3") (pinfunction "D_3") (pintype "passive"))
    )
    (net (code "122") (name "Net-(Q36-G)") (class "Default")
      (node (ref "C29") (pin "2") (pinfunction "2_2") (pintype "passive"))
      (node (ref "Q36") (pin "1") (pinfunction "G_1") (pintype "passive"))
      (node (ref "R92") (pin "1") (pinfunction "1_1") (pintype "passive"))
      (node (ref "R98") (pin "2") (pinfunction "2_2") (pintype "passive"))
    )
    (net (code "123") (name "Net-(Q37-D)") (class "Default")
      (node (ref "K13") (pin "A1") (pinfunction "A1_A1") (pintype "passive"))
      (node (ref "Q37") (pin "3") (pinfunction "D_3") (pintype "passive"))
    )
    (net (code "124") (name "Net-(Q37-G)") (class "Default")
      (node (ref "C30") (pin "2") (pinfunction "2_2") (pintype "passive"))
      (node (ref "Q37") (pin "1") (pinfunction "G_1") (pintype "passive"))
      (node (ref "R100") (pin "1") (pinfunction "1_1") (pintype "passive"))
      (node (ref "R101") (pin "2") (pinfunction "2_2") (pintype "passive"))
    )
    (net (code "125") (name "Net-(Q38-D)") (class "Default")
      (node (ref "K13") (pin "A2") (pinfunction "A2_A2") (pintype "passive"))
      (node (ref "Q38") (pin "3") (pinfunction "D_3") (pintype "passive"))
    )
    (net (code "126") (name "Net-(Q38-G)") (class "Default")
      (node (ref "C31") (pin "2") (pinfunction "2_2") (pintype "passive"))
      (node (ref "Q38") (pin "1") (pinfunction "G_1") (pintype "passive"))
      (node (ref "R102") (pin "2") (pinfunction "2_2") (pintype "passive"))
      (node (ref "R99") (pin "1") (pinfunction "1_1") (pintype "passive"))
    )
    (net (code "127") (name "Net-(Q39-D)") (class "Default")
      (node (ref "K14") (pin "A1") (pinfunction "A1_A1") (pintype "passive"))
      (node (ref "Q39") (pin "3") (pinfunction "D_3") (pintype "passive"))
    )
    (net (code "128") (name "Net-(Q39-G)") (class "Default")
      (node (ref "C32") (pin "2") (pinfunction "2_2") (pintype "passive"))
      (node (ref "Q39") (pin "1") (pinfunction "G_1") (pintype "passive"))
      (node (ref "R104") (pin "1") (pinfunction "1_1") (pintype "passive"))
      (node (ref "R105") (pin "2") (pinfunction "2_2") (pintype "passive"))
    )
    (net (code "129") (name "Net-(Q40-D)") (class "Default")
      (node (ref "K14") (pin "A2") (pinfunction "A2_A2") (pintype "passive"))
      (node (ref "Q40") (pin "3") (pinfunction "D_3") (pintype "passive"))
    )
    (net (code "130") (name "Net-(Q40-G)") (class "Default")
      (node (ref "C37") (pin "2") (pinfunction "2_2") (pintype "passive"))
      (node (ref "Q40") (pin "1") (pinfunction "G_1") (pintype "passive"))
      (node (ref "R103") (pin "1") (pinfunction "1_1") (pintype "passive"))
      (node (ref "R106") (pin "2") (pinfunction "2_2") (pintype "passive"))
    )
    (net (code "131") (name "Net-(Q41-D)") (class "Default")
      (node (ref "K15") (pin "A1") (pinfunction "A1_A1") (pintype "passive"))
      (node (ref "Q41") (pin "3") (pinfunction "D_3") (pintype "passive"))
    )
    (net (code "132") (name "Net-(Q41-G)") (class "Default")
      (node (ref "C38") (pin "2") (pinfunction "2_2") (pintype "passive"))
      (node (ref "Q41") (pin "1") (pinfunction "G_1") (pintype "passive"))
      (node (ref "R108") (pin "1") (pinfunction "1_1") (pintype "passive"))
      (node (ref "R109") (pin "2") (pinfunction "2_2") (pintype "passive"))
    )
    (net (code "133") (name "Net-(Q42-D)") (class "Default")
      (node (ref "K15") (pin "A2") (pinfunction "A2_A2") (pintype "passive"))
      (node (ref "Q42") (pin "3") (pinfunction "D_3") (pintype "passive"))
    )
    (net (code "134") (name "Net-(Q42-G)") (class "Default")
      (node (ref "C39") (pin "2") (pinfunction "2_2") (pintype "passive"))
      (node (ref "Q42") (pin "1") (pinfunction "G_1") (pintype "passive"))
      (node (ref "R107") (pin "1") (pinfunction "1_1") (pintype "passive"))
      (node (ref "R110") (pin "2") (pinfunction "2_2") (pintype "passive"))
    )
    (net (code "135") (name "Net-(Q43-D)") (class "Default")
      (node (ref "K16") (pin "A1") (pinfunction "A1_A1") (pintype "passive"))
      (node (ref "Q43") (pin "3") (pinfunction "D_3") (pintype "passive"))
    )
    (net (code "136") (name "Net-(Q43-G)") (class "Default")
      (node (ref "C40") (pin "2") (pinfunction "2_2") (pintype "passive"))
      (node (ref "Q43") (pin "1") (pinfunction "G_1") (pintype "passive"))
      (node (ref "R112") (pin "1") (pinfunction "1_1") (pintype "passive"))
      (node (ref "R113") (pin "2") (pinfunction "2_2") (pintype "passive"))
    )
    (net (code "137") (name "Net-(Q44-D)") (class "Default")
      (node (ref "K16") (pin "A2") (pinfunction "A2_A2") (pintype "passive"))
      (node (ref "Q44") (pin "3") (pinfunction "D_3") (pintype "passive"))
    )
    (net (code "138") (name "Net-(Q44-G)") (class "Default")
      (node (ref "C41") (pin "2") (pinfunction "2_2") (pintype "passive"))
      (node (ref "Q44") (pin "1") (pinfunction "G_1") (pintype "passive"))
      (node (ref "R111") (pin "1") (pinfunction "1_1") (pintype "passive"))
      (node (ref "R114") (pin "2") (pinfunction "2_2") (pintype "passive"))
    )
    (net (code "139") (name "Net-(Q45-D)") (class "Default")
      (node (ref "K17") (pin "A1") (pinfunction "A1_A1") (pintype "passive"))
      (node (ref "Q45") (pin "3") (pinfunction "D_3") (pintype "passive"))
    )
    (net (code "140") (name "Net-(Q45-G)") (class "Default")
      (node (ref "C42") (pin "2") (pinfunction "2_2") (pintype "passive"))
      (node (ref "Q45") (pin "1") (pinfunction "G_1") (pintype "passive"))
      (node (ref "R116") (pin "1") (pinfunction "1_1") (pintype "passive"))
      (node (ref "R117") (pin "2") (pinfunction "2_2") (pintype "passive"))
    )
    (net (code "141") (name "Net-(Q46-D)") (class "Default")
      (node (ref "K17") (pin "A2") (pinfunction "A2_A2") (pintype "passive"))
      (node (ref "Q46") (pin "3") (pinfunction "D_3") (pintype "passive"))
    )
    (net (code "142") (name "Net-(Q46-G)") (class "Default")
      (node (ref "C43") (pin "2") (pinfunction "2_2") (pintype "passive"))
      (node (ref "Q46") (pin "1") (pinfunction "G_1") (pintype "passive"))
      (node (ref "R115") (pin "1") (pinfunction "1_1") (pintype "passive"))
      (node (ref "R118") (pin "2") (pinfunction "2_2") (pintype "passive"))
    )
    (net (code "143") (name "Net-(Q47-D)") (class "Default")
      (node (ref "K18") (pin "A1") (pinfunction "A1_A1") (pintype "passive"))
      (node (ref "Q47") (pin "3") (pinfunction "D_3") (pintype "passive"))
    )
    (net (code "144") (name "Net-(Q47-G)") (class "Default")
      (node (ref "C44") (pin "2") (pinfunction "2_2") (pintype "passive"))
      (node (ref "Q47") (pin "1") (pinfunction "G_1") (pintype "passive"))
      (node (ref "R120") (pin "1") (pinfunction "1_1") (pintype "passive"))
      (node (ref "R121") (pin "2") (pinfunction "2_2") (pintype "passive"))
    )
    (net (code "145") (name "Net-(Q48-D)") (class "Default")
      (node (ref "K18") (pin "A2") (pinfunction "A2_A2") (pintype "passive"))
      (node (ref "Q48") (pin "3") (pinfunction "D_3") (pintype "passive"))
    )
    (net (code "146") (name "Net-(Q48-G)") (class "Default")
      (node (ref "C45") (pin "2") (pinfunction "2_2") (pintype "passive"))
      (node (ref "Q48") (pin "1") (pinfunction "G_1") (pintype "passive"))
      (node (ref "R119") (pin "1") (pinfunction "1_1") (pintype "passive"))
      (node (ref "R122") (pin "2") (pinfunction "2_2") (pintype "passive"))
    )
  )
)
